# schema_current.net
KiCad netlist of a schematic drawn in EAGLE
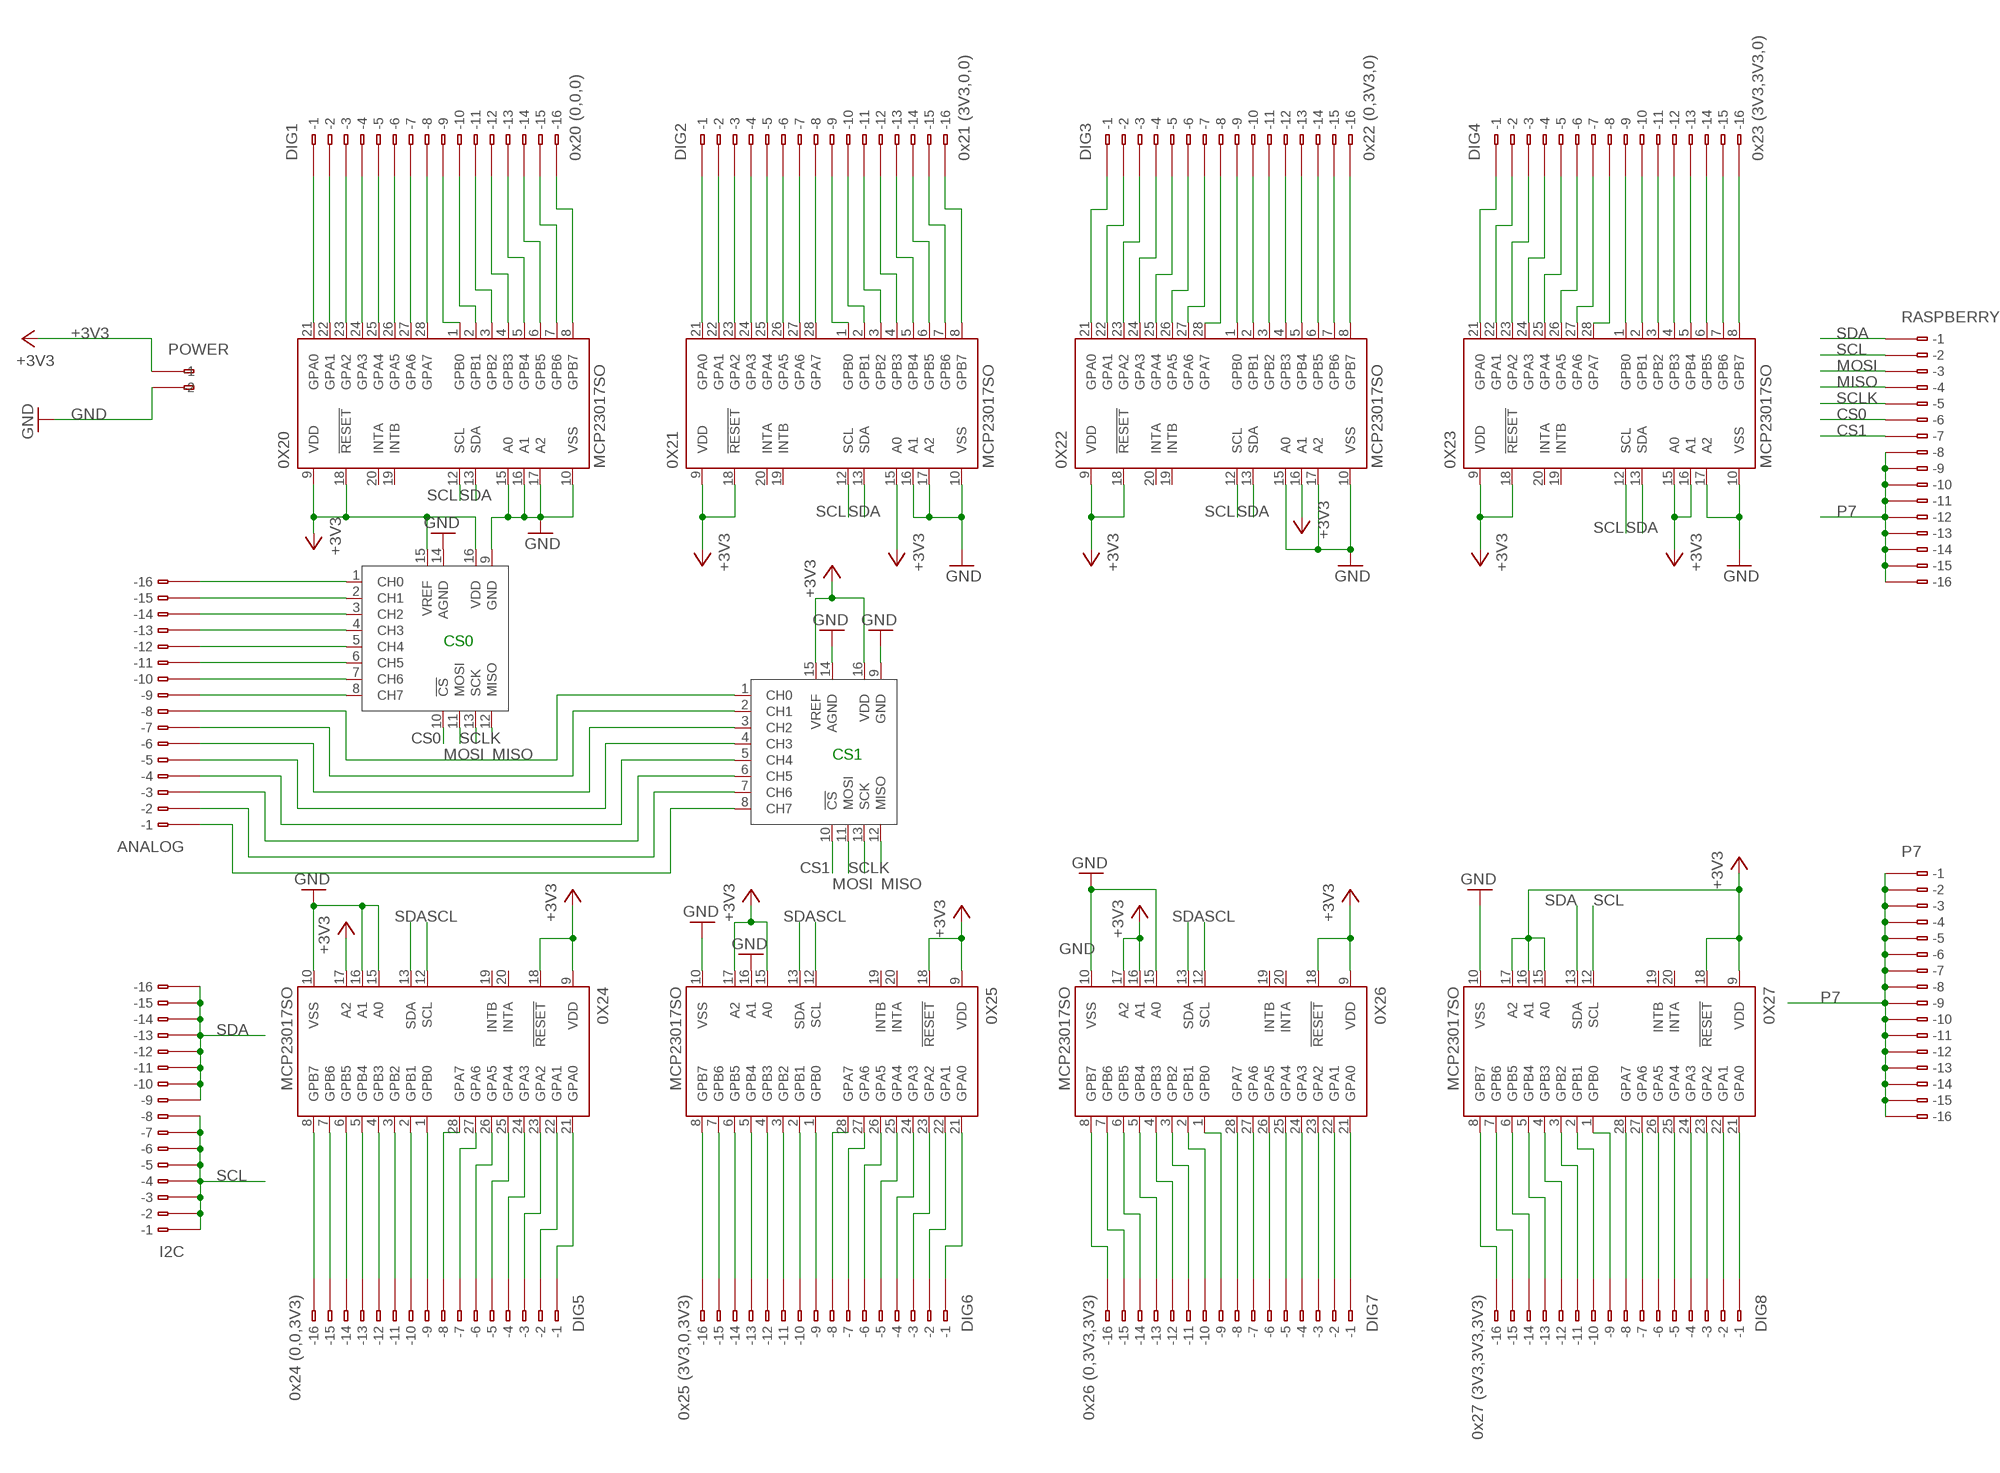
[diagram p0: schematic, sheet 1]

(export (version "E")
  (design (tool "Eeschema 10.0.6"))
  (components
    (comp (ref "0X20")
      (value "MCP23017SO")
      (footprint "eagle-import:SO28W")
      (fields (field (name "MF") "MICROCHIP") (field (name "MPN") "MCP23017-E/SO"))
      (libsource (lib "eagle-import") (part "MCP23017SO"))
    )
    (comp (ref "0X21")
      (value "MCP23017SO")
      (footprint "eagle-import:SO28W")
      (fields (field (name "MF") "MICROCHIP") (field (name "MPN") "MCP23017-E/SO"))
      (libsource (lib "eagle-import") (part "MCP23017SO"))
    )
    (comp (ref "0X22")
      (value "MCP23017SO")
      (footprint "eagle-import:SO28W")
      (fields (field (name "MF") "MICROCHIP") (field (name "MPN") "MCP23017-E/SO"))
      (libsource (lib "eagle-import") (part "MCP23017SO"))
    )
    (comp (ref "0X23")
      (value "MCP23017SO")
      (footprint "eagle-import:SO28W")
      (fields (field (name "MF") "MICROCHIP") (field (name "MPN") "MCP23017-E/SO"))
      (libsource (lib "eagle-import") (part "MCP23017SO"))
    )
    (comp (ref "0X24")
      (value "MCP23017SO")
      (footprint "eagle-import:SO28W")
      (fields (field (name "MF") "MICROCHIP") (field (name "MPN") "MCP23017-E/SO"))
      (libsource (lib "eagle-import") (part "MCP23017SO"))
    )
    (comp (ref "0X25")
      (value "MCP23017SO")
      (footprint "eagle-import:SO28W")
      (fields (field (name "MF") "MICROCHIP") (field (name "MPN") "MCP23017-E/SO"))
      (libsource (lib "eagle-import") (part "MCP23017SO"))
    )
    (comp (ref "0X26")
      (value "MCP23017SO")
      (footprint "eagle-import:SO28W")
      (fields (field (name "MF") "MICROCHIP") (field (name "MPN") "MCP23017-E/SO"))
      (libsource (lib "eagle-import") (part "MCP23017SO"))
    )
    (comp (ref "0X27")
      (value "MCP23017SO")
      (footprint "eagle-import:SO28W")
      (fields (field (name "MF") "MICROCHIP") (field (name "MPN") "MCP23017-E/SO"))
      (libsource (lib "eagle-import") (part "MCP23017SO"))
    )
    (comp (ref "ANALOG")
      (value "233-116")
      (footprint "eagle-import:233-116")
      (libsource (lib "eagle-import") (part "233-116"))
    )
    (comp (ref "DIG1")
      (value "0x20 (0,0,0)")
      (footprint "eagle-import:233-116")
      (fields (field (name "MPN") "233-116"))
      (libsource (lib "eagle-import") (part "233-116"))
    )
    (comp (ref "DIG2")
      (value "0x21 (3V3,0,0)")
      (footprint "eagle-import:233-116")
      (fields (field (name "MPN") "233-116"))
      (libsource (lib "eagle-import") (part "233-116"))
    )
    (comp (ref "DIG3")
      (value "0x22 (0,3V3,0)")
      (footprint "eagle-import:233-116")
      (fields (field (name "MPN") "233-116"))
      (libsource (lib "eagle-import") (part "233-116"))
    )
    (comp (ref "DIG4")
      (value "0x23 (3V3,3V3,0)")
      (footprint "eagle-import:233-116")
      (fields (field (name "MPN") "233-116"))
      (libsource (lib "eagle-import") (part "233-116"))
    )
    (comp (ref "DIG5")
      (value "0x24 (0,0,3V3)")
      (footprint "eagle-import:233-116")
      (fields (field (name "MPN") "233-116"))
      (libsource (lib "eagle-import") (part "233-116"))
    )
    (comp (ref "DIG6")
      (value "0x25 (3V3,0,3V3)")
      (footprint "eagle-import:233-116")
      (fields (field (name "MPN") "233-116"))
      (libsource (lib "eagle-import") (part "233-116"))
    )
    (comp (ref "DIG7")
      (value "0x26 (0,3V3,3V3)")
      (footprint "eagle-import:233-116")
      (fields (field (name "MPN") "233-116"))
      (libsource (lib "eagle-import") (part "233-116"))
    )
    (comp (ref "DIG8")
      (value "0x27 (3V3,3V3,3V3)")
      (footprint "eagle-import:233-116")
      (fields (field (name "MPN") "233-116"))
      (libsource (lib "eagle-import") (part "233-116"))
    )
    (comp (ref "I2C")
      (value "233-116")
      (footprint "eagle-import:233-116")
      (libsource (lib "eagle-import") (part "233-116"))
    )
    (comp (ref "MCP3008-CS0")
      (value "CS1")
      (footprint "eagle-import:DIL16")
      (libsource (lib "eagle-import") (part "MCP3008P"))
    )
    (comp (ref "MCP3008-CS1")
      (value "CS0")
      (footprint "eagle-import:DIL16")
      (libsource (lib "eagle-import") (part "MCP3008P"))
    )
    (comp (ref "P7")
      (value "233-116")
      (footprint "eagle-import:233-116")
      (libsource (lib "eagle-import") (part "233-116"))
    )
    (comp (ref "POWER")
      (value "233-102")
      (footprint "eagle-import:233-102")
      (libsource (lib "eagle-import") (part "233-102"))
    )
    (comp (ref "RASPBERRY")
      (value "233-116")
      (footprint "eagle-import:233-116")
      (libsource (lib "eagle-import") (part "233-116"))
    )
  )
  (nets
    (net (code "1") (name "+3V3") (class "Default")
      (node (ref "0X20") (pin "18") (pinfunction "~{RESET}_18") (pintype "input"))
      (node (ref "0X20") (pin "9") (pinfunction "VDD_9") (pintype "power_in"))
      (node (ref "0X21") (pin "15") (pinfunction "A0_15") (pintype "input"))
      (node (ref "0X21") (pin "18") (pinfunction "~{RESET}_18") (pintype "input"))
      (node (ref "0X21") (pin "9") (pinfunction "VDD_9") (pintype "power_in"))
      (node (ref "0X22") (pin "16") (pinfunction "A1_16") (pintype "input"))
      (node (ref "0X22") (pin "18") (pinfunction "~{RESET}_18") (pintype "input"))
      (node (ref "0X22") (pin "9") (pinfunction "VDD_9") (pintype "power_in"))
      (node (ref "0X23") (pin "15") (pinfunction "A0_15") (pintype "input"))
      (node (ref "0X23") (pin "16") (pinfunction "A1_16") (pintype "input"))
      (node (ref "0X23") (pin "18") (pinfunction "~{RESET}_18") (pintype "input"))
      (node (ref "0X23") (pin "9") (pinfunction "VDD_9") (pintype "power_in"))
      (node (ref "0X24") (pin "17") (pinfunction "A2_17") (pintype "input"))
      (node (ref "0X24") (pin "18") (pinfunction "~{RESET}_18") (pintype "input"))
      (node (ref "0X24") (pin "9") (pinfunction "VDD_9") (pintype "power_in"))
      (node (ref "0X25") (pin "15") (pinfunction "A0_15") (pintype "input"))
      (node (ref "0X25") (pin "17") (pinfunction "A2_17") (pintype "input"))
      (node (ref "0X25") (pin "18") (pinfunction "~{RESET}_18") (pintype "input"))
      (node (ref "0X25") (pin "9") (pinfunction "VDD_9") (pintype "power_in"))
      (node (ref "0X26") (pin "16") (pinfunction "A1_16") (pintype "input"))
      (node (ref "0X26") (pin "17") (pinfunction "A2_17") (pintype "input"))
      (node (ref "0X26") (pin "18") (pinfunction "~{RESET}_18") (pintype "input"))
      (node (ref "0X26") (pin "9") (pinfunction "VDD_9") (pintype "power_in"))
      (node (ref "0X27") (pin "15") (pinfunction "A0_15") (pintype "input"))
      (node (ref "0X27") (pin "16") (pinfunction "A1_16") (pintype "input"))
      (node (ref "0X27") (pin "17") (pinfunction "A2_17") (pintype "input"))
      (node (ref "0X27") (pin "18") (pinfunction "~{RESET}_18") (pintype "input"))
      (node (ref "0X27") (pin "9") (pinfunction "VDD_9") (pintype "power_in"))
      (node (ref "MCP3008-CS0") (pin "15") (pinfunction "VREF_15") (pintype "power_in"))
      (node (ref "MCP3008-CS0") (pin "16") (pinfunction "VDD_16") (pintype "power_in"))
      (node (ref "MCP3008-CS1") (pin "15") (pinfunction "VREF_15") (pintype "power_in"))
      (node (ref "MCP3008-CS1") (pin "16") (pinfunction "VDD_16") (pintype "power_in"))
      (node (ref "POWER") (pin "A1") (pinfunction "-1_A1") (pintype "passive"))
    )
    (net (code "2") (name "/CS0") (class "Default")
      (node (ref "MCP3008-CS0") (pin "10") (pinfunction "~{CS}_10") (pintype "input"))
      (node (ref "RASPBERRY") (pin "B6") (pinfunction "B-6_B6") (pintype "passive"))
    )
    (net (code "3") (name "/CS1") (class "Default")
      (node (ref "MCP3008-CS1") (pin "10") (pinfunction "~{CS}_10") (pintype "input"))
      (node (ref "RASPBERRY") (pin "B7") (pinfunction "B-7_B7") (pintype "passive"))
    )
    (net (code "4") (name "/MISO") (class "Default")
      (node (ref "MCP3008-CS0") (pin "12") (pinfunction "MISO_12") (pintype "output"))
      (node (ref "MCP3008-CS1") (pin "12") (pinfunction "MISO_12") (pintype "output"))
      (node (ref "RASPBERRY") (pin "B4") (pinfunction "B-4_B4") (pintype "passive"))
    )
    (net (code "5") (name "/MOSI") (class "Default")
      (node (ref "MCP3008-CS0") (pin "11") (pinfunction "MOSI_11") (pintype "input"))
      (node (ref "MCP3008-CS1") (pin "11") (pinfunction "MOSI_11") (pintype "input"))
      (node (ref "RASPBERRY") (pin "B3") (pinfunction "B-3_B3") (pintype "passive"))
    )
    (net (code "6") (name "/P7") (class "Default")
      (node (ref "P7") (pin "B1") (pinfunction "B-1_B1") (pintype "passive"))
      (node (ref "P7") (pin "B10") (pinfunction "B-10_B10") (pintype "passive"))
      (node (ref "P7") (pin "B11") (pinfunction "B-11_B11") (pintype "passive"))
      (node (ref "P7") (pin "B12") (pinfunction "B-12_B12") (pintype "passive"))
      (node (ref "P7") (pin "B13") (pinfunction "B-13_B13") (pintype "passive"))
      (node (ref "P7") (pin "B14") (pinfunction "B-14_B14") (pintype "passive"))
      (node (ref "P7") (pin "B15") (pinfunction "B-15_B15") (pintype "passive"))
      (node (ref "P7") (pin "B16") (pinfunction "B-16_B16") (pintype "passive"))
      (node (ref "P7") (pin "B2") (pinfunction "B-2_B2") (pintype "passive"))
      (node (ref "P7") (pin "B3") (pinfunction "B-3_B3") (pintype "passive"))
      (node (ref "P7") (pin "B4") (pinfunction "B-4_B4") (pintype "passive"))
      (node (ref "P7") (pin "B5") (pinfunction "B-5_B5") (pintype "passive"))
      (node (ref "P7") (pin "B6") (pinfunction "B-6_B6") (pintype "passive"))
      (node (ref "P7") (pin "B7") (pinfunction "B-7_B7") (pintype "passive"))
      (node (ref "P7") (pin "B8") (pinfunction "B-8_B8") (pintype "passive"))
      (node (ref "P7") (pin "B9") (pinfunction "B-9_B9") (pintype "passive"))
      (node (ref "RASPBERRY") (pin "B10") (pinfunction "B-10_B10") (pintype "passive"))
      (node (ref "RASPBERRY") (pin "B11") (pinfunction "B-11_B11") (pintype "passive"))
      (node (ref "RASPBERRY") (pin "B12") (pinfunction "B-12_B12") (pintype "passive"))
      (node (ref "RASPBERRY") (pin "B13") (pinfunction "B-13_B13") (pintype "passive"))
      (node (ref "RASPBERRY") (pin "B14") (pinfunction "B-14_B14") (pintype "passive"))
      (node (ref "RASPBERRY") (pin "B15") (pinfunction "B-15_B15") (pintype "passive"))
      (node (ref "RASPBERRY") (pin "B16") (pinfunction "B-16_B16") (pintype "passive"))
      (node (ref "RASPBERRY") (pin "B8") (pinfunction "B-8_B8") (pintype "passive"))
      (node (ref "RASPBERRY") (pin "B9") (pinfunction "B-9_B9") (pintype "passive"))
    )
    (net (code "7") (name "/SCL") (class "Default")
      (node (ref "0X20") (pin "12") (pinfunction "SCL_12") (pintype "input"))
      (node (ref "0X21") (pin "12") (pinfunction "SCL_12") (pintype "input"))
      (node (ref "0X22") (pin "12") (pinfunction "SCL_12") (pintype "input"))
      (node (ref "0X23") (pin "12") (pinfunction "SCL_12") (pintype "input"))
      (node (ref "0X24") (pin "12") (pinfunction "SCL_12") (pintype "input"))
      (node (ref "0X25") (pin "12") (pinfunction "SCL_12") (pintype "input"))
      (node (ref "0X26") (pin "12") (pinfunction "SCL_12") (pintype "input"))
      (node (ref "0X27") (pin "12") (pinfunction "SCL_12") (pintype "input"))
      (node (ref "I2C") (pin "B1") (pinfunction "B-1_B1") (pintype "passive"))
      (node (ref "I2C") (pin "B2") (pinfunction "B-2_B2") (pintype "passive"))
      (node (ref "I2C") (pin "B3") (pinfunction "B-3_B3") (pintype "passive"))
      (node (ref "I2C") (pin "B4") (pinfunction "B-4_B4") (pintype "passive"))
      (node (ref "I2C") (pin "B5") (pinfunction "B-5_B5") (pintype "passive"))
      (node (ref "I2C") (pin "B6") (pinfunction "B-6_B6") (pintype "passive"))
      (node (ref "I2C") (pin "B7") (pinfunction "B-7_B7") (pintype "passive"))
      (node (ref "I2C") (pin "B8") (pinfunction "B-8_B8") (pintype "passive"))
      (node (ref "RASPBERRY") (pin "B2") (pinfunction "B-2_B2") (pintype "passive"))
    )
    (net (code "8") (name "/SCLK") (class "Default")
      (node (ref "MCP3008-CS0") (pin "13") (pinfunction "SCK_13") (pintype "input"))
      (node (ref "MCP3008-CS1") (pin "13") (pinfunction "SCK_13") (pintype "input"))
      (node (ref "RASPBERRY") (pin "B5") (pinfunction "B-5_B5") (pintype "passive"))
    )
    (net (code "9") (name "/SDA") (class "Default")
      (node (ref "0X20") (pin "13") (pinfunction "SDA_13") (pintype "bidirectional"))
      (node (ref "0X21") (pin "13") (pinfunction "SDA_13") (pintype "bidirectional"))
      (node (ref "0X22") (pin "13") (pinfunction "SDA_13") (pintype "bidirectional"))
      (node (ref "0X23") (pin "13") (pinfunction "SDA_13") (pintype "bidirectional"))
      (node (ref "0X24") (pin "13") (pinfunction "SDA_13") (pintype "bidirectional"))
      (node (ref "0X25") (pin "13") (pinfunction "SDA_13") (pintype "bidirectional"))
      (node (ref "0X26") (pin "13") (pinfunction "SDA_13") (pintype "bidirectional"))
      (node (ref "0X27") (pin "13") (pinfunction "SDA_13") (pintype "bidirectional"))
      (node (ref "I2C") (pin "B10") (pinfunction "B-10_B10") (pintype "passive"))
      (node (ref "I2C") (pin "B11") (pinfunction "B-11_B11") (pintype "passive"))
      (node (ref "I2C") (pin "B12") (pinfunction "B-12_B12") (pintype "passive"))
      (node (ref "I2C") (pin "B13") (pinfunction "B-13_B13") (pintype "passive"))
      (node (ref "I2C") (pin "B14") (pinfunction "B-14_B14") (pintype "passive"))
      (node (ref "I2C") (pin "B15") (pinfunction "B-15_B15") (pintype "passive"))
      (node (ref "I2C") (pin "B16") (pinfunction "B-16_B16") (pintype "passive"))
      (node (ref "I2C") (pin "B9") (pinfunction "B-9_B9") (pintype "passive"))
      (node (ref "RASPBERRY") (pin "B1") (pinfunction "B-1_B1") (pintype "passive"))
    )
    (net (code "10") (name "GND") (class "Default")
      (node (ref "0X20") (pin "10") (pinfunction "VSS_10") (pintype "power_in"))
      (node (ref "0X20") (pin "15") (pinfunction "A0_15") (pintype "input"))
      (node (ref "0X20") (pin "16") (pinfunction "A1_16") (pintype "input"))
      (node (ref "0X20") (pin "17") (pinfunction "A2_17") (pintype "input"))
      (node (ref "0X21") (pin "10") (pinfunction "VSS_10") (pintype "power_in"))
      (node (ref "0X21") (pin "16") (pinfunction "A1_16") (pintype "input"))
      (node (ref "0X21") (pin "17") (pinfunction "A2_17") (pintype "input"))
      (node (ref "0X22") (pin "10") (pinfunction "VSS_10") (pintype "power_in"))
      (node (ref "0X22") (pin "15") (pinfunction "A0_15") (pintype "input"))
      (node (ref "0X22") (pin "17") (pinfunction "A2_17") (pintype "input"))
      (node (ref "0X23") (pin "10") (pinfunction "VSS_10") (pintype "power_in"))
      (node (ref "0X23") (pin "17") (pinfunction "A2_17") (pintype "input"))
      (node (ref "0X24") (pin "10") (pinfunction "VSS_10") (pintype "power_in"))
      (node (ref "0X24") (pin "15") (pinfunction "A0_15") (pintype "input"))
      (node (ref "0X24") (pin "16") (pinfunction "A1_16") (pintype "input"))
      (node (ref "0X25") (pin "10") (pinfunction "VSS_10") (pintype "power_in"))
      (node (ref "0X25") (pin "16") (pinfunction "A1_16") (pintype "input"))
      (node (ref "0X26") (pin "10") (pinfunction "VSS_10") (pintype "power_in"))
      (node (ref "0X26") (pin "15") (pinfunction "A0_15") (pintype "input"))
      (node (ref "0X27") (pin "10") (pinfunction "VSS_10") (pintype "power_in"))
      (node (ref "MCP3008-CS0") (pin "14") (pinfunction "AGND_14") (pintype "power_in"))
      (node (ref "MCP3008-CS0") (pin "9") (pinfunction "GND_9") (pintype "power_in"))
      (node (ref "MCP3008-CS1") (pin "14") (pinfunction "AGND_14") (pintype "power_in"))
      (node (ref "MCP3008-CS1") (pin "9") (pinfunction "GND_9") (pintype "power_in"))
      (node (ref "POWER") (pin "A2") (pinfunction "-2_A2") (pintype "passive"))
    )
    (net (code "11") (name "Net-(0X20-GPA0)") (class "Default")
      (node (ref "0X20") (pin "21") (pinfunction "GPA0_21") (pintype "bidirectional"))
      (node (ref "DIG1") (pin "B1") (pinfunction "B-1_B1") (pintype "passive"))
    )
    (net (code "12") (name "Net-(0X20-GPA1)") (class "Default")
      (node (ref "0X20") (pin "22") (pinfunction "GPA1_22") (pintype "bidirectional"))
      (node (ref "DIG1") (pin "B2") (pinfunction "B-2_B2") (pintype "passive"))
    )
    (net (code "13") (name "Net-(0X20-GPA2)") (class "Default")
      (node (ref "0X20") (pin "23") (pinfunction "GPA2_23") (pintype "bidirectional"))
      (node (ref "DIG1") (pin "B3") (pinfunction "B-3_B3") (pintype "passive"))
    )
    (net (code "14") (name "Net-(0X20-GPA3)") (class "Default")
      (node (ref "0X20") (pin "24") (pinfunction "GPA3_24") (pintype "bidirectional"))
      (node (ref "DIG1") (pin "B4") (pinfunction "B-4_B4") (pintype "passive"))
    )
    (net (code "15") (name "Net-(0X20-GPA4)") (class "Default")
      (node (ref "0X20") (pin "25") (pinfunction "GPA4_25") (pintype "bidirectional"))
      (node (ref "DIG1") (pin "B5") (pinfunction "B-5_B5") (pintype "passive"))
    )
    (net (code "16") (name "Net-(0X20-GPA5)") (class "Default")
      (node (ref "0X20") (pin "26") (pinfunction "GPA5_26") (pintype "bidirectional"))
      (node (ref "DIG1") (pin "B6") (pinfunction "B-6_B6") (pintype "passive"))
    )
    (net (code "17") (name "Net-(0X20-GPA6)") (class "Default")
      (node (ref "0X20") (pin "27") (pinfunction "GPA6_27") (pintype "bidirectional"))
      (node (ref "DIG1") (pin "B7") (pinfunction "B-7_B7") (pintype "passive"))
    )
    (net (code "18") (name "Net-(0X20-GPA7)") (class "Default")
      (node (ref "0X20") (pin "28") (pinfunction "GPA7_28") (pintype "bidirectional"))
      (node (ref "DIG1") (pin "B8") (pinfunction "B-8_B8") (pintype "passive"))
    )
    (net (code "19") (name "Net-(0X20-GPB0)") (class "Default")
      (node (ref "0X20") (pin "1") (pinfunction "GPB0_1") (pintype "bidirectional"))
      (node (ref "DIG1") (pin "B9") (pinfunction "B-9_B9") (pintype "passive"))
    )
    (net (code "20") (name "Net-(0X20-GPB1)") (class "Default")
      (node (ref "0X20") (pin "2") (pinfunction "GPB1_2") (pintype "bidirectional"))
      (node (ref "DIG1") (pin "B10") (pinfunction "B-10_B10") (pintype "passive"))
    )
    (net (code "21") (name "Net-(0X20-GPB2)") (class "Default")
      (node (ref "0X20") (pin "3") (pinfunction "GPB2_3") (pintype "bidirectional"))
      (node (ref "DIG1") (pin "B11") (pinfunction "B-11_B11") (pintype "passive"))
    )
    (net (code "22") (name "Net-(0X20-GPB3)") (class "Default")
      (node (ref "0X20") (pin "4") (pinfunction "GPB3_4") (pintype "bidirectional"))
      (node (ref "DIG1") (pin "B12") (pinfunction "B-12_B12") (pintype "passive"))
    )
    (net (code "23") (name "Net-(0X20-GPB4)") (class "Default")
      (node (ref "0X20") (pin "5") (pinfunction "GPB4_5") (pintype "bidirectional"))
      (node (ref "DIG1") (pin "B13") (pinfunction "B-13_B13") (pintype "passive"))
    )
    (net (code "24") (name "Net-(0X20-GPB5)") (class "Default")
      (node (ref "0X20") (pin "6") (pinfunction "GPB5_6") (pintype "bidirectional"))
      (node (ref "DIG1") (pin "B14") (pinfunction "B-14_B14") (pintype "passive"))
    )
    (net (code "25") (name "Net-(0X20-GPB6)") (class "Default")
      (node (ref "0X20") (pin "7") (pinfunction "GPB6_7") (pintype "bidirectional"))
      (node (ref "DIG1") (pin "B15") (pinfunction "B-15_B15") (pintype "passive"))
    )
    (net (code "26") (name "Net-(0X20-GPB7)") (class "Default")
      (node (ref "0X20") (pin "8") (pinfunction "GPB7_8") (pintype "bidirectional"))
      (node (ref "DIG1") (pin "B16") (pinfunction "B-16_B16") (pintype "passive"))
    )
    (net (code "27") (name "Net-(0X21-GPA0)") (class "Default")
      (node (ref "0X21") (pin "21") (pinfunction "GPA0_21") (pintype "bidirectional"))
      (node (ref "DIG2") (pin "B1") (pinfunction "B-1_B1") (pintype "passive"))
    )
    (net (code "28") (name "Net-(0X21-GPA1)") (class "Default")
      (node (ref "0X21") (pin "22") (pinfunction "GPA1_22") (pintype "bidirectional"))
      (node (ref "DIG2") (pin "B2") (pinfunction "B-2_B2") (pintype "passive"))
    )
    (net (code "29") (name "Net-(0X21-GPA2)") (class "Default")
      (node (ref "0X21") (pin "23") (pinfunction "GPA2_23") (pintype "bidirectional"))
      (node (ref "DIG2") (pin "B3") (pinfunction "B-3_B3") (pintype "passive"))
    )
    (net (code "30") (name "Net-(0X21-GPA3)") (class "Default")
      (node (ref "0X21") (pin "24") (pinfunction "GPA3_24") (pintype "bidirectional"))
      (node (ref "DIG2") (pin "B4") (pinfunction "B-4_B4") (pintype "passive"))
    )
    (net (code "31") (name "Net-(0X21-GPA4)") (class "Default")
      (node (ref "0X21") (pin "25") (pinfunction "GPA4_25") (pintype "bidirectional"))
      (node (ref "DIG2") (pin "B5") (pinfunction "B-5_B5") (pintype "passive"))
    )
    (net (code "32") (name "Net-(0X21-GPA5)") (class "Default")
      (node (ref "0X21") (pin "26") (pinfunction "GPA5_26") (pintype "bidirectional"))
      (node (ref "DIG2") (pin "B6") (pinfunction "B-6_B6") (pintype "passive"))
    )
    (net (code "33") (name "Net-(0X21-GPA6)") (class "Default")
      (node (ref "0X21") (pin "27") (pinfunction "GPA6_27") (pintype "bidirectional"))
      (node (ref "DIG2") (pin "B7") (pinfunction "B-7_B7") (pintype "passive"))
    )
    (net (code "34") (name "Net-(0X21-GPA7)") (class "Default")
      (node (ref "0X21") (pin "28") (pinfunction "GPA7_28") (pintype "bidirectional"))
      (node (ref "DIG2") (pin "B8") (pinfunction "B-8_B8") (pintype "passive"))
    )
    (net (code "35") (name "Net-(0X21-GPB0)") (class "Default")
      (node (ref "0X21") (pin "1") (pinfunction "GPB0_1") (pintype "bidirectional"))
      (node (ref "DIG2") (pin "B9") (pinfunction "B-9_B9") (pintype "passive"))
    )
    (net (code "36") (name "Net-(0X21-GPB1)") (class "Default")
      (node (ref "0X21") (pin "2") (pinfunction "GPB1_2") (pintype "bidirectional"))
      (node (ref "DIG2") (pin "B10") (pinfunction "B-10_B10") (pintype "passive"))
    )
    (net (code "37") (name "Net-(0X21-GPB2)") (class "Default")
      (node (ref "0X21") (pin "3") (pinfunction "GPB2_3") (pintype "bidirectional"))
      (node (ref "DIG2") (pin "B11") (pinfunction "B-11_B11") (pintype "passive"))
    )
    (net (code "38") (name "Net-(0X21-GPB3)") (class "Default")
      (node (ref "0X21") (pin "4") (pinfunction "GPB3_4") (pintype "bidirectional"))
      (node (ref "DIG2") (pin "B12") (pinfunction "B-12_B12") (pintype "passive"))
    )
    (net (code "39") (name "Net-(0X21-GPB4)") (class "Default")
      (node (ref "0X21") (pin "5") (pinfunction "GPB4_5") (pintype "bidirectional"))
      (node (ref "DIG2") (pin "B13") (pinfunction "B-13_B13") (pintype "passive"))
    )
    (net (code "40") (name "Net-(0X21-GPB5)") (class "Default")
      (node (ref "0X21") (pin "6") (pinfunction "GPB5_6") (pintype "bidirectional"))
      (node (ref "DIG2") (pin "B14") (pinfunction "B-14_B14") (pintype "passive"))
    )
    (net (code "41") (name "Net-(0X21-GPB6)") (class "Default")
      (node (ref "0X21") (pin "7") (pinfunction "GPB6_7") (pintype "bidirectional"))
      (node (ref "DIG2") (pin "B15") (pinfunction "B-15_B15") (pintype "passive"))
    )
    (net (code "42") (name "Net-(0X21-GPB7)") (class "Default")
      (node (ref "0X21") (pin "8") (pinfunction "GPB7_8") (pintype "bidirectional"))
      (node (ref "DIG2") (pin "B16") (pinfunction "B-16_B16") (pintype "passive"))
    )
    (net (code "43") (name "Net-(0X22-GPA0)") (class "Default")
      (node (ref "0X22") (pin "21") (pinfunction "GPA0_21") (pintype "bidirectional"))
      (node (ref "DIG3") (pin "B1") (pinfunction "B-1_B1") (pintype "passive"))
    )
    (net (code "44") (name "Net-(0X22-GPA1)") (class "Default")
      (node (ref "0X22") (pin "22") (pinfunction "GPA1_22") (pintype "bidirectional"))
      (node (ref "DIG3") (pin "B2") (pinfunction "B-2_B2") (pintype "passive"))
    )
    (net (code "45") (name "Net-(0X22-GPA2)") (class "Default")
      (node (ref "0X22") (pin "23") (pinfunction "GPA2_23") (pintype "bidirectional"))
      (node (ref "DIG3") (pin "B3") (pinfunction "B-3_B3") (pintype "passive"))
    )
    (net (code "46") (name "Net-(0X22-GPA3)") (class "Default")
      (node (ref "0X22") (pin "24") (pinfunction "GPA3_24") (pintype "bidirectional"))
      (node (ref "DIG3") (pin "B4") (pinfunction "B-4_B4") (pintype "passive"))
    )
    (net (code "47") (name "Net-(0X22-GPA4)") (class "Default")
      (node (ref "0X22") (pin "25") (pinfunction "GPA4_25") (pintype "bidirectional"))
      (node (ref "DIG3") (pin "B5") (pinfunction "B-5_B5") (pintype "passive"))
    )
    (net (code "48") (name "Net-(0X22-GPA5)") (class "Default")
      (node (ref "0X22") (pin "26") (pinfunction "GPA5_26") (pintype "bidirectional"))
      (node (ref "DIG3") (pin "B6") (pinfunction "B-6_B6") (pintype "passive"))
    )
    (net (code "49") (name "Net-(0X22-GPA6)") (class "Default")
      (node (ref "0X22") (pin "27") (pinfunction "GPA6_27") (pintype "bidirectional"))
      (node (ref "DIG3") (pin "B7") (pinfunction "B-7_B7") (pintype "passive"))
    )
    (net (code "50") (name "Net-(0X22-GPA7)") (class "Default")
      (node (ref "0X22") (pin "28") (pinfunction "GPA7_28") (pintype "bidirectional"))
      (node (ref "DIG3") (pin "B8") (pinfunction "B-8_B8") (pintype "passive"))
    )
    (net (code "51") (name "Net-(0X22-GPB0)") (class "Default")
      (node (ref "0X22") (pin "1") (pinfunction "GPB0_1") (pintype "bidirectional"))
      (node (ref "DIG3") (pin "B9") (pinfunction "B-9_B9") (pintype "passive"))
    )
    (net (code "52") (name "Net-(0X22-GPB1)") (class "Default")
      (node (ref "0X22") (pin "2") (pinfunction "GPB1_2") (pintype "bidirectional"))
      (node (ref "DIG3") (pin "B10") (pinfunction "B-10_B10") (pintype "passive"))
    )
    (net (code "53") (name "Net-(0X22-GPB2)") (class "Default")
      (node (ref "0X22") (pin "3") (pinfunction "GPB2_3") (pintype "bidirectional"))
      (node (ref "DIG3") (pin "B11") (pinfunction "B-11_B11") (pintype "passive"))
    )
    (net (code "54") (name "Net-(0X22-GPB3)") (class "Default")
      (node (ref "0X22") (pin "4") (pinfunction "GPB3_4") (pintype "bidirectional"))
      (node (ref "DIG3") (pin "B12") (pinfunction "B-12_B12") (pintype "passive"))
    )
    (net (code "55") (name "Net-(0X22-GPB4)") (class "Default")
      (node (ref "0X22") (pin "5") (pinfunction "GPB4_5") (pintype "bidirectional"))
      (node (ref "DIG3") (pin "B13") (pinfunction "B-13_B13") (pintype "passive"))
    )
    (net (code "56") (name "Net-(0X22-GPB5)") (class "Default")
      (node (ref "0X22") (pin "6") (pinfunction "GPB5_6") (pintype "bidirectional"))
      (node (ref "DIG3") (pin "B14") (pinfunction "B-14_B14") (pintype "passive"))
    )
    (net (code "57") (name "Net-(0X22-GPB6)") (class "Default")
      (node (ref "0X22") (pin "7") (pinfunction "GPB6_7") (pintype "bidirectional"))
      (node (ref "DIG3") (pin "B15") (pinfunction "B-15_B15") (pintype "passive"))
    )
    (net (code "58") (name "Net-(0X22-GPB7)") (class "Default")
      (node (ref "0X22") (pin "8") (pinfunction "GPB7_8") (pintype "bidirectional"))
      (node (ref "DIG3") (pin "B16") (pinfunction "B-16_B16") (pintype "passive"))
    )
    (net (code "59") (name "Net-(0X23-GPA0)") (class "Default")
      (node (ref "0X23") (pin "21") (pinfunction "GPA0_21") (pintype "bidirectional"))
      (node (ref "DIG4") (pin "B1") (pinfunction "B-1_B1") (pintype "passive"))
    )
    (net (code "60") (name "Net-(0X23-GPA1)") (class "Default")
      (node (ref "0X23") (pin "22") (pinfunction "GPA1_22") (pintype "bidirectional"))
      (node (ref "DIG4") (pin "B2") (pinfunction "B-2_B2") (pintype "passive"))
    )
    (net (code "61") (name "Net-(0X23-GPA2)") (class "Default")
      (node (ref "0X23") (pin "23") (pinfunction "GPA2_23") (pintype "bidirectional"))
      (node (ref "DIG4") (pin "B3") (pinfunction "B-3_B3") (pintype "passive"))
    )
    (net (code "62") (name "Net-(0X23-GPA3)") (class "Default")
      (node (ref "0X23") (pin "24") (pinfunction "GPA3_24") (pintype "bidirectional"))
      (node (ref "DIG4") (pin "B4") (pinfunction "B-4_B4") (pintype "passive"))
    )
    (net (code "63") (name "Net-(0X23-GPA4)") (class "Default")
      (node (ref "0X23") (pin "25") (pinfunction "GPA4_25") (pintype "bidirectional"))
      (node (ref "DIG4") (pin "B5") (pinfunction "B-5_B5") (pintype "passive"))
    )
    (net (code "64") (name "Net-(0X23-GPA5)") (class "Default")
      (node (ref "0X23") (pin "26") (pinfunction "GPA5_26") (pintype "bidirectional"))
      (node (ref "DIG4") (pin "B6") (pinfunction "B-6_B6") (pintype "passive"))
    )
    (net (code "65") (name "Net-(0X23-GPA6)") (class "Default")
      (node (ref "0X23") (pin "27") (pinfunction "GPA6_27") (pintype "bidirectional"))
      (node (ref "DIG4") (pin "B7") (pinfunction "B-7_B7") (pintype "passive"))
    )
    (net (code "66") (name "Net-(0X23-GPA7)") (class "Default")
      (node (ref "0X23") (pin "28") (pinfunction "GPA7_28") (pintype "bidirectional"))
      (node (ref "DIG4") (pin "B8") (pinfunction "B-8_B8") (pintype "passive"))
    )
    (net (code "67") (name "Net-(0X23-GPB0)") (class "Default")
      (node (ref "0X23") (pin "1") (pinfunction "GPB0_1") (pintype "bidirectional"))
      (node (ref "DIG4") (pin "B9") (pinfunction "B-9_B9") (pintype "passive"))
    )
    (net (code "68") (name "Net-(0X23-GPB1)") (class "Default")
      (node (ref "0X23") (pin "2") (pinfunction "GPB1_2") (pintype "bidirectional"))
      (node (ref "DIG4") (pin "B10") (pinfunction "B-10_B10") (pintype "passive"))
    )
    (net (code "69") (name "Net-(0X23-GPB2)") (class "Default")
      (node (ref "0X23") (pin "3") (pinfunction "GPB2_3") (pintype "bidirectional"))
      (node (ref "DIG4") (pin "B11") (pinfunction "B-11_B11") (pintype "passive"))
    )
    (net (code "70") (name "Net-(0X23-GPB3)") (class "Default")
      (node (ref "0X23") (pin "4") (pinfunction "GPB3_4") (pintype "bidirectional"))
      (node (ref "DIG4") (pin "B12") (pinfunction "B-12_B12") (pintype "passive"))
    )
    (net (code "71") (name "Net-(0X23-GPB4)") (class "Default")
      (node (ref "0X23") (pin "5") (pinfunction "GPB4_5") (pintype "bidirectional"))
      (node (ref "DIG4") (pin "B13") (pinfunction "B-13_B13") (pintype "passive"))
    )
    (net (code "72") (name "Net-(0X23-GPB5)") (class "Default")
      (node (ref "0X23") (pin "6") (pinfunction "GPB5_6") (pintype "bidirectional"))
      (node (ref "DIG4") (pin "B14") (pinfunction "B-14_B14") (pintype "passive"))
    )
    (net (code "73") (name "Net-(0X23-GPB6)") (class "Default")
      (node (ref "0X23") (pin "7") (pinfunction "GPB6_7") (pintype "bidirectional"))
      (node (ref "DIG4") (pin "B15") (pinfunction "B-15_B15") (pintype "passive"))
    )
    (net (code "74") (name "Net-(0X23-GPB7)") (class "Default")
      (node (ref "0X23") (pin "8") (pinfunction "GPB7_8") (pintype "bidirectional"))
      (node (ref "DIG4") (pin "B16") (pinfunction "B-16_B16") (pintype "passive"))
    )
    (net (code "75") (name "Net-(0X24-GPA0)") (class "Default")
      (node (ref "0X24") (pin "21") (pinfunction "GPA0_21") (pintype "bidirectional"))
      (node (ref "DIG5") (pin "B1") (pinfunction "B-1_B1") (pintype "passive"))
    )
    (net (code "76") (name "Net-(0X24-GPA1)") (class "Default")
      (node (ref "0X24") (pin "22") (pinfunction "GPA1_22") (pintype "bidirectional"))
      (node (ref "DIG5") (pin "B2") (pinfunction "B-2_B2") (pintype "passive"))
    )
    (net (code "77") (name "Net-(0X24-GPA2)") (class "Default")
      (node (ref "0X24") (pin "23") (pinfunction "GPA2_23") (pintype "bidirectional"))
      (node (ref "DIG5") (pin "B3") (pinfunction "B-3_B3") (pintype "passive"))
    )
    (net (code "78") (name "Net-(0X24-GPA3)") (class "Default")
      (node (ref "0X24") (pin "24") (pinfunction "GPA3_24") (pintype "bidirectional"))
      (node (ref "DIG5") (pin "B4") (pinfunction "B-4_B4") (pintype "passive"))
    )
    (net (code "79") (name "Net-(0X24-GPA4)") (class "Default")
      (node (ref "0X24") (pin "25") (pinfunction "GPA4_25") (pintype "bidirectional"))
      (node (ref "DIG5") (pin "B5") (pinfunction "B-5_B5") (pintype "passive"))
    )
    (net (code "80") (name "Net-(0X24-GPA5)") (class "Default")
      (node (ref "0X24") (pin "26") (pinfunction "GPA5_26") (pintype "bidirectional"))
      (node (ref "DIG5") (pin "B6") (pinfunction "B-6_B6") (pintype "passive"))
    )
    (net (code "81") (name "Net-(0X24-GPA6)") (class "Default")
      (node (ref "0X24") (pin "27") (pinfunction "GPA6_27") (pintype "bidirectional"))
      (node (ref "DIG5") (pin "B7") (pinfunction "B-7_B7") (pintype "passive"))
    )
    (net (code "82") (name "Net-(0X24-GPA7)") (class "Default")
      (node (ref "0X24") (pin "28") (pinfunction "GPA7_28") (pintype "bidirectional"))
      (node (ref "DIG5") (pin "B8") (pinfunction "B-8_B8") (pintype "passive"))
    )
    (net (code "83") (name "Net-(0X24-GPB0)") (class "Default")
      (node (ref "0X24") (pin "1") (pinfunction "GPB0_1") (pintype "bidirectional"))
      (node (ref "DIG5") (pin "B9") (pinfunction "B-9_B9") (pintype "passive"))
    )
    (net (code "84") (name "Net-(0X24-GPB1)") (class "Default")
      (node (ref "0X24") (pin "2") (pinfunction "GPB1_2") (pintype "bidirectional"))
      (node (ref "DIG5") (pin "B10") (pinfunction "B-10_B10") (pintype "passive"))
    )
    (net (code "85") (name "Net-(0X24-GPB2)") (class "Default")
      (node (ref "0X24") (pin "3") (pinfunction "GPB2_3") (pintype "bidirectional"))
      (node (ref "DIG5") (pin "B11") (pinfunction "B-11_B11") (pintype "passive"))
    )
    (net (code "86") (name "Net-(0X24-GPB3)") (class "Default")
      (node (ref "0X24") (pin "4") (pinfunction "GPB3_4") (pintype "bidirectional"))
      (node (ref "DIG5") (pin "B12") (pinfunction "B-12_B12") (pintype "passive"))
    )
    (net (code "87") (name "Net-(0X24-GPB4)") (class "Default")
      (node (ref "0X24") (pin "5") (pinfunction "GPB4_5") (pintype "bidirectional"))
      (node (ref "DIG5") (pin "B13") (pinfunction "B-13_B13") (pintype "passive"))
    )
    (net (code "88") (name "Net-(0X24-GPB5)") (class "Default")
      (node (ref "0X24") (pin "6") (pinfunction "GPB5_6") (pintype "bidirectional"))
      (node (ref "DIG5") (pin "B14") (pinfunction "B-14_B14") (pintype "passive"))
    )
    (net (code "89") (name "Net-(0X24-GPB6)") (class "Default")
      (node (ref "0X24") (pin "7") (pinfunction "GPB6_7") (pintype "bidirectional"))
      (node (ref "DIG5") (pin "B15") (pinfunction "B-15_B15") (pintype "passive"))
    )
    (net (code "90") (name "Net-(0X24-GPB7)") (class "Default")
      (node (ref "0X24") (pin "8") (pinfunction "GPB7_8") (pintype "bidirectional"))
      (node (ref "DIG5") (pin "B16") (pinfunction "B-16_B16") (pintype "passive"))
    )
    (net (code "91") (name "Net-(0X25-GPA0)") (class "Default")
      (node (ref "0X25") (pin "21") (pinfunction "GPA0_21") (pintype "bidirectional"))
      (node (ref "DIG6") (pin "B1") (pinfunction "B-1_B1") (pintype "passive"))
    )
    (net (code "92") (name "Net-(0X25-GPA1)") (class "Default")
      (node (ref "0X25") (pin "22") (pinfunction "GPA1_22") (pintype "bidirectional"))
      (node (ref "DIG6") (pin "B2") (pinfunction "B-2_B2") (pintype "passive"))
    )
    (net (code "93") (name "Net-(0X25-GPA2)") (class "Default")
      (node (ref "0X25") (pin "23") (pinfunction "GPA2_23") (pintype "bidirectional"))
      (node (ref "DIG6") (pin "B3") (pinfunction "B-3_B3") (pintype "passive"))
    )
    (net (code "94") (name "Net-(0X25-GPA3)") (class "Default")
      (node (ref "0X25") (pin "24") (pinfunction "GPA3_24") (pintype "bidirectional"))
      (node (ref "DIG6") (pin "B4") (pinfunction "B-4_B4") (pintype "passive"))
    )
    (net (code "95") (name "Net-(0X25-GPA4)") (class "Default")
      (node (ref "0X25") (pin "25") (pinfunction "GPA4_25") (pintype "bidirectional"))
      (node (ref "DIG6") (pin "B5") (pinfunction "B-5_B5") (pintype "passive"))
    )
    (net (code "96") (name "Net-(0X25-GPA5)") (class "Default")
      (node (ref "0X25") (pin "26") (pinfunction "GPA5_26") (pintype "bidirectional"))
      (node (ref "DIG6") (pin "B6") (pinfunction "B-6_B6") (pintype "passive"))
    )
    (net (code "97") (name "Net-(0X25-GPA6)") (class "Default")
      (node (ref "0X25") (pin "27") (pinfunction "GPA6_27") (pintype "bidirectional"))
      (node (ref "DIG6") (pin "B7") (pinfunction "B-7_B7") (pintype "passive"))
    )
    (net (code "98") (name "Net-(0X25-GPA7)") (class "Default")
      (node (ref "0X25") (pin "28") (pinfunction "GPA7_28") (pintype "bidirectional"))
      (node (ref "DIG6") (pin "B8") (pinfunction "B-8_B8") (pintype "passive"))
    )
    (net (code "99") (name "Net-(0X25-GPB0)") (class "Default")
      (node (ref "0X25") (pin "1") (pinfunction "GPB0_1") (pintype "bidirectional"))
      (node (ref "DIG6") (pin "B9") (pinfunction "B-9_B9") (pintype "passive"))
    )
    (net (code "100") (name "Net-(0X25-GPB1)") (class "Default")
      (node (ref "0X25") (pin "2") (pinfunction "GPB1_2") (pintype "bidirectional"))
      (node (ref "DIG6") (pin "B10") (pinfunction "B-10_B10") (pintype "passive"))
    )
    (net (code "101") (name "Net-(0X25-GPB2)") (class "Default")
      (node (ref "0X25") (pin "3") (pinfunction "GPB2_3") (pintype "bidirectional"))
      (node (ref "DIG6") (pin "B11") (pinfunction "B-11_B11") (pintype "passive"))
    )
    (net (code "102") (name "Net-(0X25-GPB3)") (class "Default")
      (node (ref "0X25") (pin "4") (pinfunction "GPB3_4") (pintype "bidirectional"))
      (node (ref "DIG6") (pin "B12") (pinfunction "B-12_B12") (pintype "passive"))
    )
    (net (code "103") (name "Net-(0X25-GPB4)") (class "Default")
      (node (ref "0X25") (pin "5") (pinfunction "GPB4_5") (pintype "bidirectional"))
      (node (ref "DIG6") (pin "B13") (pinfunction "B-13_B13") (pintype "passive"))
    )
    (net (code "104") (name "Net-(0X25-GPB5)") (class "Default")
      (node (ref "0X25") (pin "6") (pinfunction "GPB5_6") (pintype "bidirectional"))
      (node (ref "DIG6") (pin "B14") (pinfunction "B-14_B14") (pintype "passive"))
    )
    (net (code "105") (name "Net-(0X25-GPB6)") (class "Default")
      (node (ref "0X25") (pin "7") (pinfunction "GPB6_7") (pintype "bidirectional"))
      (node (ref "DIG6") (pin "B15") (pinfunction "B-15_B15") (pintype "passive"))
    )
    (net (code "106") (name "Net-(0X25-GPB7)") (class "Default")
      (node (ref "0X25") (pin "8") (pinfunction "GPB7_8") (pintype "bidirectional"))
      (node (ref "DIG6") (pin "B16") (pinfunction "B-16_B16") (pintype "passive"))
    )
    (net (code "107") (name "Net-(0X26-GPA0)") (class "Default")
      (node (ref "0X26") (pin "21") (pinfunction "GPA0_21") (pintype "bidirectional"))
      (node (ref "DIG7") (pin "B1") (pinfunction "B-1_B1") (pintype "passive"))
    )
    (net (code "108") (name "Net-(0X26-GPA1)") (class "Default")
      (node (ref "0X26") (pin "22") (pinfunction "GPA1_22") (pintype "bidirectional"))
      (node (ref "DIG7") (pin "B2") (pinfunction "B-2_B2") (pintype "passive"))
    )
    (net (code "109") (name "Net-(0X26-GPA2)") (class "Default")
      (node (ref "0X26") (pin "23") (pinfunction "GPA2_23") (pintype "bidirectional"))
      (node (ref "DIG7") (pin "B3") (pinfunction "B-3_B3") (pintype "passive"))
    )
    (net (code "110") (name "Net-(0X26-GPA3)") (class "Default")
      (node (ref "0X26") (pin "24") (pinfunction "GPA3_24") (pintype "bidirectional"))
      (node (ref "DIG7") (pin "B4") (pinfunction "B-4_B4") (pintype "passive"))
    )
    (net (code "111") (name "Net-(0X26-GPA4)") (class "Default")
      (node (ref "0X26") (pin "25") (pinfunction "GPA4_25") (pintype "bidirectional"))
      (node (ref "DIG7") (pin "B5") (pinfunction "B-5_B5") (pintype "passive"))
    )
    (net (code "112") (name "Net-(0X26-GPA5)") (class "Default")
      (node (ref "0X26") (pin "26") (pinfunction "GPA5_26") (pintype "bidirectional"))
      (node (ref "DIG7") (pin "B6") (pinfunction "B-6_B6") (pintype "passive"))
    )
    (net (code "113") (name "Net-(0X26-GPA6)") (class "Default")
      (node (ref "0X26") (pin "27") (pinfunction "GPA6_27") (pintype "bidirectional"))
      (node (ref "DIG7") (pin "B7") (pinfunction "B-7_B7") (pintype "passive"))
    )
    (net (code "114") (name "Net-(0X26-GPA7)") (class "Default")
      (node (ref "0X26") (pin "28") (pinfunction "GPA7_28") (pintype "bidirectional"))
      (node (ref "DIG7") (pin "B8") (pinfunction "B-8_B8") (pintype "passive"))
    )
    (net (code "115") (name "Net-(0X26-GPB0)") (class "Default")
      (node (ref "0X26") (pin "1") (pinfunction "GPB0_1") (pintype "bidirectional"))
      (node (ref "DIG7") (pin "B9") (pinfunction "B-9_B9") (pintype "passive"))
    )
    (net (code "116") (name "Net-(0X26-GPB1)") (class "Default")
      (node (ref "0X26") (pin "2") (pinfunction "GPB1_2") (pintype "bidirectional"))
      (node (ref "DIG7") (pin "B10") (pinfunction "B-10_B10") (pintype "passive"))
    )
    (net (code "117") (name "Net-(0X26-GPB2)") (class "Default")
      (node (ref "0X26") (pin "3") (pinfunction "GPB2_3") (pintype "bidirectional"))
      (node (ref "DIG7") (pin "B11") (pinfunction "B-11_B11") (pintype "passive"))
    )
    (net (code "118") (name "Net-(0X26-GPB3)") (class "Default")
      (node (ref "0X26") (pin "4") (pinfunction "GPB3_4") (pintype "bidirectional"))
      (node (ref "DIG7") (pin "B12") (pinfunction "B-12_B12") (pintype "passive"))
    )
    (net (code "119") (name "Net-(0X26-GPB4)") (class "Default")
      (node (ref "0X26") (pin "5") (pinfunction "GPB4_5") (pintype "bidirectional"))
      (node (ref "DIG7") (pin "B13") (pinfunction "B-13_B13") (pintype "passive"))
    )
    (net (code "120") (name "Net-(0X26-GPB5)") (class "Default")
      (node (ref "0X26") (pin "6") (pinfunction "GPB5_6") (pintype "bidirectional"))
      (node (ref "DIG7") (pin "B14") (pinfunction "B-14_B14") (pintype "passive"))
    )
    (net (code "121") (name "Net-(0X26-GPB6)") (class "Default")
      (node (ref "0X26") (pin "7") (pinfunction "GPB6_7") (pintype "bidirectional"))
      (node (ref "DIG7") (pin "B15") (pinfunction "B-15_B15") (pintype "passive"))
    )
    (net (code "122") (name "Net-(0X26-GPB7)") (class "Default")
      (node (ref "0X26") (pin "8") (pinfunction "GPB7_8") (pintype "bidirectional"))
      (node (ref "DIG7") (pin "B16") (pinfunction "B-16_B16") (pintype "passive"))
    )
    (net (code "123") (name "Net-(0X27-GPA0)") (class "Default")
      (node (ref "0X27") (pin "21") (pinfunction "GPA0_21") (pintype "bidirectional"))
      (node (ref "DIG8") (pin "B1") (pinfunction "B-1_B1") (pintype "passive"))
    )
    (net (code "124") (name "Net-(0X27-GPA1)") (class "Default")
      (node (ref "0X27") (pin "22") (pinfunction "GPA1_22") (pintype "bidirectional"))
      (node (ref "DIG8") (pin "B2") (pinfunction "B-2_B2") (pintype "passive"))
    )
    (net (code "125") (name "Net-(0X27-GPA2)") (class "Default")
      (node (ref "0X27") (pin "23") (pinfunction "GPA2_23") (pintype "bidirectional"))
      (node (ref "DIG8") (pin "B3") (pinfunction "B-3_B3") (pintype "passive"))
    )
    (net (code "126") (name "Net-(0X27-GPA3)") (class "Default")
      (node (ref "0X27") (pin "24") (pinfunction "GPA3_24") (pintype "bidirectional"))
      (node (ref "DIG8") (pin "B4") (pinfunction "B-4_B4") (pintype "passive"))
    )
    (net (code "127") (name "Net-(0X27-GPA4)") (class "Default")
      (node (ref "0X27") (pin "25") (pinfunction "GPA4_25") (pintype "bidirectional"))
      (node (ref "DIG8") (pin "B5") (pinfunction "B-5_B5") (pintype "passive"))
    )
    (net (code "128") (name "Net-(0X27-GPA5)") (class "Default")
      (node (ref "0X27") (pin "26") (pinfunction "GPA5_26") (pintype "bidirectional"))
      (node (ref "DIG8") (pin "B6") (pinfunction "B-6_B6") (pintype "passive"))
    )
    (net (code "129") (name "Net-(0X27-GPA6)") (class "Default")
      (node (ref "0X27") (pin "27") (pinfunction "GPA6_27") (pintype "bidirectional"))
      (node (ref "DIG8") (pin "B7") (pinfunction "B-7_B7") (pintype "passive"))
    )
    (net (code "130") (name "Net-(0X27-GPA7)") (class "Default")
      (node (ref "0X27") (pin "28") (pinfunction "GPA7_28") (pintype "bidirectional"))
      (node (ref "DIG8") (pin "B8") (pinfunction "B-8_B8") (pintype "passive"))
    )
    (net (code "131") (name "Net-(0X27-GPB0)") (class "Default")
      (node (ref "0X27") (pin "1") (pinfunction "GPB0_1") (pintype "bidirectional"))
      (node (ref "DIG8") (pin "B9") (pinfunction "B-9_B9") (pintype "passive"))
    )
    (net (code "132") (name "Net-(0X27-GPB1)") (class "Default")
      (node (ref "0X27") (pin "2") (pinfunction "GPB1_2") (pintype "bidirectional"))
      (node (ref "DIG8") (pin "B10") (pinfunction "B-10_B10") (pintype "passive"))
    )
    (net (code "133") (name "Net-(0X27-GPB2)") (class "Default")
      (node (ref "0X27") (pin "3") (pinfunction "GPB2_3") (pintype "bidirectional"))
      (node (ref "DIG8") (pin "B11") (pinfunction "B-11_B11") (pintype "passive"))
    )
    (net (code "134") (name "Net-(0X27-GPB3)") (class "Default")
      (node (ref "0X27") (pin "4") (pinfunction "GPB3_4") (pintype "bidirectional"))
      (node (ref "DIG8") (pin "B12") (pinfunction "B-12_B12") (pintype "passive"))
    )
    (net (code "135") (name "Net-(0X27-GPB4)") (class "Default")
      (node (ref "0X27") (pin "5") (pinfunction "GPB4_5") (pintype "bidirectional"))
      (node (ref "DIG8") (pin "B13") (pinfunction "B-13_B13") (pintype "passive"))
    )
    (net (code "136") (name "Net-(0X27-GPB5)") (class "Default")
      (node (ref "0X27") (pin "6") (pinfunction "GPB5_6") (pintype "bidirectional"))
      (node (ref "DIG8") (pin "B14") (pinfunction "B-14_B14") (pintype "passive"))
    )
    (net (code "137") (name "Net-(0X27-GPB6)") (class "Default")
      (node (ref "0X27") (pin "7") (pinfunction "GPB6_7") (pintype "bidirectional"))
      (node (ref "DIG8") (pin "B15") (pinfunction "B-15_B15") (pintype "passive"))
    )
    (net (code "138") (name "Net-(0X27-GPB7)") (class "Default")
      (node (ref "0X27") (pin "8") (pinfunction "GPB7_8") (pintype "bidirectional"))
      (node (ref "DIG8") (pin "B16") (pinfunction "B-16_B16") (pintype "passive"))
    )
    (net (code "139") (name "Net-(ANALOG-B-1)") (class "Default")
      (node (ref "ANALOG") (pin "B1") (pinfunction "B-1_B1") (pintype "passive"))
      (node (ref "MCP3008-CS1") (pin "8") (pinfunction "CH7_8") (pintype "input"))
    )
    (net (code "140") (name "Net-(ANALOG-B-2)") (class "Default")
      (node (ref "ANALOG") (pin "B2") (pinfunction "B-2_B2") (pintype "passive"))
      (node (ref "MCP3008-CS1") (pin "7") (pinfunction "CH6_7") (pintype "input"))
    )
    (net (code "141") (name "Net-(ANALOG-B-3)") (class "Default")
      (node (ref "ANALOG") (pin "B3") (pinfunction "B-3_B3") (pintype "passive"))
      (node (ref "MCP3008-CS1") (pin "6") (pinfunction "CH5_6") (pintype "input"))
    )
    (net (code "142") (name "Net-(ANALOG-B-4)") (class "Default")
      (node (ref "ANALOG") (pin "B4") (pinfunction "B-4_B4") (pintype "passive"))
      (node (ref "MCP3008-CS1") (pin "5") (pinfunction "CH4_5") (pintype "input"))
    )
    (net (code "143") (name "Net-(ANALOG-B-5)") (class "Default")
      (node (ref "ANALOG") (pin "B5") (pinfunction "B-5_B5") (pintype "passive"))
      (node (ref "MCP3008-CS1") (pin "4") (pinfunction "CH3_4") (pintype "input"))
    )
    (net (code "144") (name "Net-(ANALOG-B-6)") (class "Default")
      (node (ref "ANALOG") (pin "B6") (pinfunction "B-6_B6") (pintype "passive"))
      (node (ref "MCP3008-CS1") (pin "3") (pinfunction "CH2_3") (pintype "input"))
    )
    (net (code "145") (name "Net-(ANALOG-B-7)") (class "Default")
      (node (ref "ANALOG") (pin "B7") (pinfunction "B-7_B7") (pintype "passive"))
      (node (ref "MCP3008-CS1") (pin "2") (pinfunction "CH1_2") (pintype "input"))
    )
    (net (code "146") (name "Net-(ANALOG-B-8)") (class "Default")
      (node (ref "ANALOG") (pin "B8") (pinfunction "B-8_B8") (pintype "passive"))
      (node (ref "MCP3008-CS1") (pin "1") (pinfunction "CH0_1") (pintype "input"))
    )
    (net (code "147") (name "Net-(ANALOG-B-9)") (class "Default")
      (node (ref "ANALOG") (pin "B9") (pinfunction "B-9_B9") (pintype "passive"))
      (node (ref "MCP3008-CS0") (pin "8") (pinfunction "CH7_8") (pintype "input"))
    )
    (net (code "148") (name "Net-(ANALOG-B-10)") (class "Default")
      (node (ref "ANALOG") (pin "B10") (pinfunction "B-10_B10") (pintype "passive"))
      (node (ref "MCP3008-CS0") (pin "7") (pinfunction "CH6_7") (pintype "input"))
    )
    (net (code "149") (name "Net-(ANALOG-B-11)") (class "Default")
      (node (ref "ANALOG") (pin "B11") (pinfunction "B-11_B11") (pintype "passive"))
      (node (ref "MCP3008-CS0") (pin "6") (pinfunction "CH5_6") (pintype "input"))
    )
    (net (code "150") (name "Net-(ANALOG-B-12)") (class "Default")
      (node (ref "ANALOG") (pin "B12") (pinfunction "B-12_B12") (pintype "passive"))
      (node (ref "MCP3008-CS0") (pin "5") (pinfunction "CH4_5") (pintype "input"))
    )
    (net (code "151") (name "Net-(ANALOG-B-13)") (class "Default")
      (node (ref "ANALOG") (pin "B13") (pinfunction "B-13_B13") (pintype "passive"))
      (node (ref "MCP3008-CS0") (pin "4") (pinfunction "CH3_4") (pintype "input"))
    )
    (net (code "152") (name "Net-(ANALOG-B-14)") (class "Default")
      (node (ref "ANALOG") (pin "B14") (pinfunction "B-14_B14") (pintype "passive"))
      (node (ref "MCP3008-CS0") (pin "3") (pinfunction "CH2_3") (pintype "input"))
    )
    (net (code "153") (name "Net-(ANALOG-B-15)") (class "Default")
      (node (ref "ANALOG") (pin "B15") (pinfunction "B-15_B15") (pintype "passive"))
      (node (ref "MCP3008-CS0") (pin "2") (pinfunction "CH1_2") (pintype "input"))
    )
    (net (code "154") (name "Net-(ANALOG-B-16)") (class "Default")
      (node (ref "ANALOG") (pin "B16") (pinfunction "B-16_B16") (pintype "passive"))
      (node (ref "MCP3008-CS0") (pin "1") (pinfunction "CH0_1") (pintype "input"))
    )
    (net (code "155") (name "unconnected-(0X20-INTA-Pad20)") (class "Default")
      (node (ref "0X20") (pin "20") (pinfunction "INTA_20") (pintype "output"))
    )
    (net (code "156") (name "unconnected-(0X20-INTB-Pad19)") (class "Default")
      (node (ref "0X20") (pin "19") (pinfunction "INTB_19") (pintype "output"))
    )
    (net (code "157") (name "unconnected-(0X21-INTA-Pad20)") (class "Default")
      (node (ref "0X21") (pin "20") (pinfunction "INTA_20") (pintype "output"))
    )
    (net (code "158") (name "unconnected-(0X21-INTB-Pad19)") (class "Default")
      (node (ref "0X21") (pin "19") (pinfunction "INTB_19") (pintype "output"))
    )
    (net (code "159") (name "unconnected-(0X22-INTA-Pad20)") (class "Default")
      (node (ref "0X22") (pin "20") (pinfunction "INTA_20") (pintype "output"))
    )
    (net (code "160") (name "unconnected-(0X22-INTB-Pad19)") (class "Default")
      (node (ref "0X22") (pin "19") (pinfunction "INTB_19") (pintype "output"))
    )
    (net (code "161") (name "unconnected-(0X23-INTA-Pad20)") (class "Default")
      (node (ref "0X23") (pin "20") (pinfunction "INTA_20") (pintype "output"))
    )
    (net (code "162") (name "unconnected-(0X23-INTB-Pad19)") (class "Default")
      (node (ref "0X23") (pin "19") (pinfunction "INTB_19") (pintype "output"))
    )
    (net (code "163") (name "unconnected-(0X24-INTA-Pad20)") (class "Default")
      (node (ref "0X24") (pin "20") (pinfunction "INTA_20") (pintype "output"))
    )
    (net (code "164") (name "unconnected-(0X24-INTB-Pad19)") (class "Default")
      (node (ref "0X24") (pin "19") (pinfunction "INTB_19") (pintype "output"))
    )
    (net (code "165") (name "unconnected-(0X25-INTA-Pad20)") (class "Default")
      (node (ref "0X25") (pin "20") (pinfunction "INTA_20") (pintype "output"))
    )
    (net (code "166") (name "unconnected-(0X25-INTB-Pad19)") (class "Default")
      (node (ref "0X25") (pin "19") (pinfunction "INTB_19") (pintype "output"))
    )
    (net (code "167") (name "unconnected-(0X26-INTA-Pad20)") (class "Default")
      (node (ref "0X26") (pin "20") (pinfunction "INTA_20") (pintype "output"))
    )
    (net (code "168") (name "unconnected-(0X26-INTB-Pad19)") (class "Default")
      (node (ref "0X26") (pin "19") (pinfunction "INTB_19") (pintype "output"))
    )
    (net (code "169") (name "unconnected-(0X27-INTA-Pad20)") (class "Default")
      (node (ref "0X27") (pin "20") (pinfunction "INTA_20") (pintype "output"))
    )
    (net (code "170") (name "unconnected-(0X27-INTB-Pad19)") (class "Default")
      (node (ref "0X27") (pin "19") (pinfunction "INTB_19") (pintype "output"))
    )
    (net (code "171") (name "unconnected-(ANALOG--1-PadA1)") (class "Default")
      (node (ref "ANALOG") (pin "A1") (pinfunction "-1_A1") (pintype "passive"))
    )
    (net (code "172") (name "unconnected-(ANALOG--2-PadA2)") (class "Default")
      (node (ref "ANALOG") (pin "A2") (pinfunction "-2_A2") (pintype "passive"))
    )
    (net (code "173") (name "unconnected-(ANALOG--3-PadA3)") (class "Default")
      (node (ref "ANALOG") (pin "A3") (pinfunction "-3_A3") (pintype "passive"))
    )
    (net (code "174") (name "unconnected-(ANALOG--4-PadA4)") (class "Default")
      (node (ref "ANALOG") (pin "A4") (pinfunction "-4_A4") (pintype "passive"))
    )
    (net (code "175") (name "unconnected-(ANALOG--5-PadA5)") (class "Default")
      (node (ref "ANALOG") (pin "A5") (pinfunction "-5_A5") (pintype "passive"))
    )
    (net (code "176") (name "unconnected-(ANALOG--6-PadA6)") (class "Default")
      (node (ref "ANALOG") (pin "A6") (pinfunction "-6_A6") (pintype "passive"))
    )
    (net (code "177") (name "unconnected-(ANALOG--7-PadA7)") (class "Default")
      (node (ref "ANALOG") (pin "A7") (pinfunction "-7_A7") (pintype "passive"))
    )
    (net (code "178") (name "unconnected-(ANALOG--8-PadA8)") (class "Default")
      (node (ref "ANALOG") (pin "A8") (pinfunction "-8_A8") (pintype "passive"))
    )
    (net (code "179") (name "unconnected-(ANALOG--9-PadA9)") (class "Default")
      (node (ref "ANALOG") (pin "A9") (pinfunction "-9_A9") (pintype "passive"))
    )
    (net (code "180") (name "unconnected-(ANALOG--10-PadA10)") (class "Default")
      (node (ref "ANALOG") (pin "A10") (pinfunction "-10_A10") (pintype "passive"))
    )
    (net (code "181") (name "unconnected-(ANALOG--11-PadA11)") (class "Default")
      (node (ref "ANALOG") (pin "A11") (pinfunction "-11_A11") (pintype "passive"))
    )
    (net (code "182") (name "unconnected-(ANALOG--12-PadA12)") (class "Default")
      (node (ref "ANALOG") (pin "A12") (pinfunction "-12_A12") (pintype "passive"))
    )
    (net (code "183") (name "unconnected-(ANALOG--13-PadA13)") (class "Default")
      (node (ref "ANALOG") (pin "A13") (pinfunction "-13_A13") (pintype "passive"))
    )
    (net (code "184") (name "unconnected-(ANALOG--14-PadA14)") (class "Default")
      (node (ref "ANALOG") (pin "A14") (pinfunction "-14_A14") (pintype "passive"))
    )
    (net (code "185") (name "unconnected-(ANALOG--15-PadA15)") (class "Default")
      (node (ref "ANALOG") (pin "A15") (pinfunction "-15_A15") (pintype "passive"))
    )
    (net (code "186") (name "unconnected-(ANALOG--16-PadA16)") (class "Default")
      (node (ref "ANALOG") (pin "A16") (pinfunction "-16_A16") (pintype "passive"))
    )
    (net (code "187") (name "unconnected-(DIG1--1-PadA1)") (class "Default")
      (node (ref "DIG1") (pin "A1") (pinfunction "-1_A1") (pintype "passive"))
    )
    (net (code "188") (name "unconnected-(DIG1--2-PadA2)") (class "Default")
      (node (ref "DIG1") (pin "A2") (pinfunction "-2_A2") (pintype "passive"))
    )
    (net (code "189") (name "unconnected-(DIG1--3-PadA3)") (class "Default")
      (node (ref "DIG1") (pin "A3") (pinfunction "-3_A3") (pintype "passive"))
    )
    (net (code "190") (name "unconnected-(DIG1--4-PadA4)") (class "Default")
      (node (ref "DIG1") (pin "A4") (pinfunction "-4_A4") (pintype "passive"))
    )
    (net (code "191") (name "unconnected-(DIG1--5-PadA5)") (class "Default")
      (node (ref "DIG1") (pin "A5") (pinfunction "-5_A5") (pintype "passive"))
    )
    (net (code "192") (name "unconnected-(DIG1--6-PadA6)") (class "Default")
      (node (ref "DIG1") (pin "A6") (pinfunction "-6_A6") (pintype "passive"))
    )
    (net (code "193") (name "unconnected-(DIG1--7-PadA7)") (class "Default")
      (node (ref "DIG1") (pin "A7") (pinfunction "-7_A7") (pintype "passive"))
    )
    (net (code "194") (name "unconnected-(DIG1--8-PadA8)") (class "Default")
      (node (ref "DIG1") (pin "A8") (pinfunction "-8_A8") (pintype "passive"))
    )
    (net (code "195") (name "unconnected-(DIG1--9-PadA9)") (class "Default")
      (node (ref "DIG1") (pin "A9") (pinfunction "-9_A9") (pintype "passive"))
    )
    (net (code "196") (name "unconnected-(DIG1--10-PadA10)") (class "Default")
      (node (ref "DIG1") (pin "A10") (pinfunction "-10_A10") (pintype "passive"))
    )
    (net (code "197") (name "unconnected-(DIG1--11-PadA11)") (class "Default")
      (node (ref "DIG1") (pin "A11") (pinfunction "-11_A11") (pintype "passive"))
    )
    (net (code "198") (name "unconnected-(DIG1--12-PadA12)") (class "Default")
      (node (ref "DIG1") (pin "A12") (pinfunction "-12_A12") (pintype "passive"))
    )
    (net (code "199") (name "unconnected-(DIG1--13-PadA13)") (class "Default")
      (node (ref "DIG1") (pin "A13") (pinfunction "-13_A13") (pintype "passive"))
    )
    (net (code "200") (name "unconnected-(DIG1--14-PadA14)") (class "Default")
      (node (ref "DIG1") (pin "A14") (pinfunction "-14_A14") (pintype "passive"))
    )
    (net (code "201") (name "unconnected-(DIG1--15-PadA15)") (class "Default")
      (node (ref "DIG1") (pin "A15") (pinfunction "-15_A15") (pintype "passive"))
    )
    (net (code "202") (name "unconnected-(DIG1--16-PadA16)") (class "Default")
      (node (ref "DIG1") (pin "A16") (pinfunction "-16_A16") (pintype "passive"))
    )
    (net (code "203") (name "unconnected-(DIG2--1-PadA1)") (class "Default")
      (node (ref "DIG2") (pin "A1") (pinfunction "-1_A1") (pintype "passive"))
    )
    (net (code "204") (name "unconnected-(DIG2--2-PadA2)") (class "Default")
      (node (ref "DIG2") (pin "A2") (pinfunction "-2_A2") (pintype "passive"))
    )
    (net (code "205") (name "unconnected-(DIG2--3-PadA3)") (class "Default")
      (node (ref "DIG2") (pin "A3") (pinfunction "-3_A3") (pintype "passive"))
    )
    (net (code "206") (name "unconnected-(DIG2--4-PadA4)") (class "Default")
      (node (ref "DIG2") (pin "A4") (pinfunction "-4_A4") (pintype "passive"))
    )
    (net (code "207") (name "unconnected-(DIG2--5-PadA5)") (class "Default")
      (node (ref "DIG2") (pin "A5") (pinfunction "-5_A5") (pintype "passive"))
    )
    (net (code "208") (name "unconnected-(DIG2--6-PadA6)") (class "Default")
      (node (ref "DIG2") (pin "A6") (pinfunction "-6_A6") (pintype "passive"))
    )
    (net (code "209") (name "unconnected-(DIG2--7-PadA7)") (class "Default")
      (node (ref "DIG2") (pin "A7") (pinfunction "-7_A7") (pintype "passive"))
    )
    (net (code "210") (name "unconnected-(DIG2--8-PadA8)") (class "Default")
      (node (ref "DIG2") (pin "A8") (pinfunction "-8_A8") (pintype "passive"))
    )
    (net (code "211") (name "unconnected-(DIG2--9-PadA9)") (class "Default")
      (node (ref "DIG2") (pin "A9") (pinfunction "-9_A9") (pintype "passive"))
    )
    (net (code "212") (name "unconnected-(DIG2--10-PadA10)") (class "Default")
      (node (ref "DIG2") (pin "A10") (pinfunction "-10_A10") (pintype "passive"))
    )
    (net (code "213") (name "unconnected-(DIG2--11-PadA11)") (class "Default")
      (node (ref "DIG2") (pin "A11") (pinfunction "-11_A11") (pintype "passive"))
    )
    (net (code "214") (name "unconnected-(DIG2--12-PadA12)") (class "Default")
      (node (ref "DIG2") (pin "A12") (pinfunction "-12_A12") (pintype "passive"))
    )
    (net (code "215") (name "unconnected-(DIG2--13-PadA13)") (class "Default")
      (node (ref "DIG2") (pin "A13") (pinfunction "-13_A13") (pintype "passive"))
    )
    (net (code "216") (name "unconnected-(DIG2--14-PadA14)") (class "Default")
      (node (ref "DIG2") (pin "A14") (pinfunction "-14_A14") (pintype "passive"))
    )
    (net (code "217") (name "unconnected-(DIG2--15-PadA15)") (class "Default")
      (node (ref "DIG2") (pin "A15") (pinfunction "-15_A15") (pintype "passive"))
    )
    (net (code "218") (name "unconnected-(DIG2--16-PadA16)") (class "Default")
      (node (ref "DIG2") (pin "A16") (pinfunction "-16_A16") (pintype "passive"))
    )
    (net (code "219") (name "unconnected-(DIG3--1-PadA1)") (class "Default")
      (node (ref "DIG3") (pin "A1") (pinfunction "-1_A1") (pintype "passive"))
    )
    (net (code "220") (name "unconnected-(DIG3--2-PadA2)") (class "Default")
      (node (ref "DIG3") (pin "A2") (pinfunction "-2_A2") (pintype "passive"))
    )
    (net (code "221") (name "unconnected-(DIG3--3-PadA3)") (class "Default")
      (node (ref "DIG3") (pin "A3") (pinfunction "-3_A3") (pintype "passive"))
    )
    (net (code "222") (name "unconnected-(DIG3--4-PadA4)") (class "Default")
      (node (ref "DIG3") (pin "A4") (pinfunction "-4_A4") (pintype "passive"))
    )
    (net (code "223") (name "unconnected-(DIG3--5-PadA5)") (class "Default")
      (node (ref "DIG3") (pin "A5") (pinfunction "-5_A5") (pintype "passive"))
    )
    (net (code "224") (name "unconnected-(DIG3--6-PadA6)") (class "Default")
      (node (ref "DIG3") (pin "A6") (pinfunction "-6_A6") (pintype "passive"))
    )
    (net (code "225") (name "unconnected-(DIG3--7-PadA7)") (class "Default")
      (node (ref "DIG3") (pin "A7") (pinfunction "-7_A7") (pintype "passive"))
    )
    (net (code "226") (name "unconnected-(DIG3--8-PadA8)") (class "Default")
      (node (ref "DIG3") (pin "A8") (pinfunction "-8_A8") (pintype "passive"))
    )
    (net (code "227") (name "unconnected-(DIG3--9-PadA9)") (class "Default")
      (node (ref "DIG3") (pin "A9") (pinfunction "-9_A9") (pintype "passive"))
    )
    (net (code "228") (name "unconnected-(DIG3--10-PadA10)") (class "Default")
      (node (ref "DIG3") (pin "A10") (pinfunction "-10_A10") (pintype "passive"))
    )
    (net (code "229") (name "unconnected-(DIG3--11-PadA11)") (class "Default")
      (node (ref "DIG3") (pin "A11") (pinfunction "-11_A11") (pintype "passive"))
    )
    (net (code "230") (name "unconnected-(DIG3--12-PadA12)") (class "Default")
      (node (ref "DIG3") (pin "A12") (pinfunction "-12_A12") (pintype "passive"))
    )
    (net (code "231") (name "unconnected-(DIG3--13-PadA13)") (class "Default")
      (node (ref "DIG3") (pin "A13") (pinfunction "-13_A13") (pintype "passive"))
    )
    (net (code "232") (name "unconnected-(DIG3--14-PadA14)") (class "Default")
      (node (ref "DIG3") (pin "A14") (pinfunction "-14_A14") (pintype "passive"))
    )
    (net (code "233") (name "unconnected-(DIG3--15-PadA15)") (class "Default")
      (node (ref "DIG3") (pin "A15") (pinfunction "-15_A15") (pintype "passive"))
    )
    (net (code "234") (name "unconnected-(DIG3--16-PadA16)") (class "Default")
      (node (ref "DIG3") (pin "A16") (pinfunction "-16_A16") (pintype "passive"))
    )
    (net (code "235") (name "unconnected-(DIG4--1-PadA1)") (class "Default")
      (node (ref "DIG4") (pin "A1") (pinfunction "-1_A1") (pintype "passive"))
    )
    (net (code "236") (name "unconnected-(DIG4--2-PadA2)") (class "Default")
      (node (ref "DIG4") (pin "A2") (pinfunction "-2_A2") (pintype "passive"))
    )
    (net (code "237") (name "unconnected-(DIG4--3-PadA3)") (class "Default")
      (node (ref "DIG4") (pin "A3") (pinfunction "-3_A3") (pintype "passive"))
    )
    (net (code "238") (name "unconnected-(DIG4--4-PadA4)") (class "Default")
      (node (ref "DIG4") (pin "A4") (pinfunction "-4_A4") (pintype "passive"))
    )
    (net (code "239") (name "unconnected-(DIG4--5-PadA5)") (class "Default")
      (node (ref "DIG4") (pin "A5") (pinfunction "-5_A5") (pintype "passive"))
    )
    (net (code "240") (name "unconnected-(DIG4--6-PadA6)") (class "Default")
      (node (ref "DIG4") (pin "A6") (pinfunction "-6_A6") (pintype "passive"))
    )
    (net (code "241") (name "unconnected-(DIG4--7-PadA7)") (class "Default")
      (node (ref "DIG4") (pin "A7") (pinfunction "-7_A7") (pintype "passive"))
    )
    (net (code "242") (name "unconnected-(DIG4--8-PadA8)") (class "Default")
      (node (ref "DIG4") (pin "A8") (pinfunction "-8_A8") (pintype "passive"))
    )
    (net (code "243") (name "unconnected-(DIG4--9-PadA9)") (class "Default")
      (node (ref "DIG4") (pin "A9") (pinfunction "-9_A9") (pintype "passive"))
    )
    (net (code "244") (name "unconnected-(DIG4--10-PadA10)") (class "Default")
      (node (ref "DIG4") (pin "A10") (pinfunction "-10_A10") (pintype "passive"))
    )
    (net (code "245") (name "unconnected-(DIG4--11-PadA11)") (class "Default")
      (node (ref "DIG4") (pin "A11") (pinfunction "-11_A11") (pintype "passive"))
    )
    (net (code "246") (name "unconnected-(DIG4--12-PadA12)") (class "Default")
      (node (ref "DIG4") (pin "A12") (pinfunction "-12_A12") (pintype "passive"))
    )
    (net (code "247") (name "unconnected-(DIG4--13-PadA13)") (class "Default")
      (node (ref "DIG4") (pin "A13") (pinfunction "-13_A13") (pintype "passive"))
    )
    (net (code "248") (name "unconnected-(DIG4--14-PadA14)") (class "Default")
      (node (ref "DIG4") (pin "A14") (pinfunction "-14_A14") (pintype "passive"))
    )
    (net (code "249") (name "unconnected-(DIG4--15-PadA15)") (class "Default")
      (node (ref "DIG4") (pin "A15") (pinfunction "-15_A15") (pintype "passive"))
    )
    (net (code "250") (name "unconnected-(DIG4--16-PadA16)") (class "Default")
      (node (ref "DIG4") (pin "A16") (pinfunction "-16_A16") (pintype "passive"))
    )
    (net (code "251") (name "unconnected-(DIG5--1-PadA1)") (class "Default")
      (node (ref "DIG5") (pin "A1") (pinfunction "-1_A1") (pintype "passive"))
    )
    (net (code "252") (name "unconnected-(DIG5--2-PadA2)") (class "Default")
      (node (ref "DIG5") (pin "A2") (pinfunction "-2_A2") (pintype "passive"))
    )
    (net (code "253") (name "unconnected-(DIG5--3-PadA3)") (class "Default")
      (node (ref "DIG5") (pin "A3") (pinfunction "-3_A3") (pintype "passive"))
    )
    (net (code "254") (name "unconnected-(DIG5--4-PadA4)") (class "Default")
      (node (ref "DIG5") (pin "A4") (pinfunction "-4_A4") (pintype "passive"))
    )
    (net (code "255") (name "unconnected-(DIG5--5-PadA5)") (class "Default")
      (node (ref "DIG5") (pin "A5") (pinfunction "-5_A5") (pintype "passive"))
    )
    (net (code "256") (name "unconnected-(DIG5--6-PadA6)") (class "Default")
      (node (ref "DIG5") (pin "A6") (pinfunction "-6_A6") (pintype "passive"))
    )
    (net (code "257") (name "unconnected-(DIG5--7-PadA7)") (class "Default")
      (node (ref "DIG5") (pin "A7") (pinfunction "-7_A7") (pintype "passive"))
    )
    (net (code "258") (name "unconnected-(DIG5--8-PadA8)") (class "Default")
      (node (ref "DIG5") (pin "A8") (pinfunction "-8_A8") (pintype "passive"))
    )
    (net (code "259") (name "unconnected-(DIG5--9-PadA9)") (class "Default")
      (node (ref "DIG5") (pin "A9") (pinfunction "-9_A9") (pintype "passive"))
    )
    (net (code "260") (name "unconnected-(DIG5--10-PadA10)") (class "Default")
      (node (ref "DIG5") (pin "A10") (pinfunction "-10_A10") (pintype "passive"))
    )
    (net (code "261") (name "unconnected-(DIG5--11-PadA11)") (class "Default")
      (node (ref "DIG5") (pin "A11") (pinfunction "-11_A11") (pintype "passive"))
    )
    (net (code "262") (name "unconnected-(DIG5--12-PadA12)") (class "Default")
      (node (ref "DIG5") (pin "A12") (pinfunction "-12_A12") (pintype "passive"))
    )
    (net (code "263") (name "unconnected-(DIG5--13-PadA13)") (class "Default")
      (node (ref "DIG5") (pin "A13") (pinfunction "-13_A13") (pintype "passive"))
    )
    (net (code "264") (name "unconnected-(DIG5--14-PadA14)") (class "Default")
      (node (ref "DIG5") (pin "A14") (pinfunction "-14_A14") (pintype "passive"))
    )
    (net (code "265") (name "unconnected-(DIG5--15-PadA15)") (class "Default")
      (node (ref "DIG5") (pin "A15") (pinfunction "-15_A15") (pintype "passive"))
    )
    (net (code "266") (name "unconnected-(DIG5--16-PadA16)") (class "Default")
      (node (ref "DIG5") (pin "A16") (pinfunction "-16_A16") (pintype "passive"))
    )
    (net (code "267") (name "unconnected-(DIG6--1-PadA1)") (class "Default")
      (node (ref "DIG6") (pin "A1") (pinfunction "-1_A1") (pintype "passive"))
    )
    (net (code "268") (name "unconnected-(DIG6--2-PadA2)") (class "Default")
      (node (ref "DIG6") (pin "A2") (pinfunction "-2_A2") (pintype "passive"))
    )
    (net (code "269") (name "unconnected-(DIG6--3-PadA3)") (class "Default")
      (node (ref "DIG6") (pin "A3") (pinfunction "-3_A3") (pintype "passive"))
    )
    (net (code "270") (name "unconnected-(DIG6--4-PadA4)") (class "Default")
      (node (ref "DIG6") (pin "A4") (pinfunction "-4_A4") (pintype "passive"))
    )
    (net (code "271") (name "unconnected-(DIG6--5-PadA5)") (class "Default")
      (node (ref "DIG6") (pin "A5") (pinfunction "-5_A5") (pintype "passive"))
    )
    (net (code "272") (name "unconnected-(DIG6--6-PadA6)") (class "Default")
      (node (ref "DIG6") (pin "A6") (pinfunction "-6_A6") (pintype "passive"))
    )
    (net (code "273") (name "unconnected-(DIG6--7-PadA7)") (class "Default")
      (node (ref "DIG6") (pin "A7") (pinfunction "-7_A7") (pintype "passive"))
    )
    (net (code "274") (name "unconnected-(DIG6--8-PadA8)") (class "Default")
      (node (ref "DIG6") (pin "A8") (pinfunction "-8_A8") (pintype "passive"))
    )
    (net (code "275") (name "unconnected-(DIG6--9-PadA9)") (class "Default")
      (node (ref "DIG6") (pin "A9") (pinfunction "-9_A9") (pintype "passive"))
    )
    (net (code "276") (name "unconnected-(DIG6--10-PadA10)") (class "Default")
      (node (ref "DIG6") (pin "A10") (pinfunction "-10_A10") (pintype "passive"))
    )
    (net (code "277") (name "unconnected-(DIG6--11-PadA11)") (class "Default")
      (node (ref "DIG6") (pin "A11") (pinfunction "-11_A11") (pintype "passive"))
    )
    (net (code "278") (name "unconnected-(DIG6--12-PadA12)") (class "Default")
      (node (ref "DIG6") (pin "A12") (pinfunction "-12_A12") (pintype "passive"))
    )
    (net (code "279") (name "unconnected-(DIG6--13-PadA13)") (class "Default")
      (node (ref "DIG6") (pin "A13") (pinfunction "-13_A13") (pintype "passive"))
    )
    (net (code "280") (name "unconnected-(DIG6--14-PadA14)") (class "Default")
      (node (ref "DIG6") (pin "A14") (pinfunction "-14_A14") (pintype "passive"))
    )
    (net (code "281") (name "unconnected-(DIG6--15-PadA15)") (class "Default")
      (node (ref "DIG6") (pin "A15") (pinfunction "-15_A15") (pintype "passive"))
    )
    (net (code "282") (name "unconnected-(DIG6--16-PadA16)") (class "Default")
      (node (ref "DIG6") (pin "A16") (pinfunction "-16_A16") (pintype "passive"))
    )
    (net (code "283") (name "unconnected-(DIG7--1-PadA1)") (class "Default")
      (node (ref "DIG7") (pin "A1") (pinfunction "-1_A1") (pintype "passive"))
    )
    (net (code "284") (name "unconnected-(DIG7--2-PadA2)") (class "Default")
      (node (ref "DIG7") (pin "A2") (pinfunction "-2_A2") (pintype "passive"))
    )
    (net (code "285") (name "unconnected-(DIG7--3-PadA3)") (class "Default")
      (node (ref "DIG7") (pin "A3") (pinfunction "-3_A3") (pintype "passive"))
    )
    (net (code "286") (name "unconnected-(DIG7--4-PadA4)") (class "Default")
      (node (ref "DIG7") (pin "A4") (pinfunction "-4_A4") (pintype "passive"))
    )
    (net (code "287") (name "unconnected-(DIG7--5-PadA5)") (class "Default")
      (node (ref "DIG7") (pin "A5") (pinfunction "-5_A5") (pintype "passive"))
    )
    (net (code "288") (name "unconnected-(DIG7--6-PadA6)") (class "Default")
      (node (ref "DIG7") (pin "A6") (pinfunction "-6_A6") (pintype "passive"))
    )
    (net (code "289") (name "unconnected-(DIG7--7-PadA7)") (class "Default")
      (node (ref "DIG7") (pin "A7") (pinfunction "-7_A7") (pintype "passive"))
    )
    (net (code "290") (name "unconnected-(DIG7--8-PadA8)") (class "Default")
      (node (ref "DIG7") (pin "A8") (pinfunction "-8_A8") (pintype "passive"))
    )
    (net (code "291") (name "unconnected-(DIG7--9-PadA9)") (class "Default")
      (node (ref "DIG7") (pin "A9") (pinfunction "-9_A9") (pintype "passive"))
    )
    (net (code "292") (name "unconnected-(DIG7--10-PadA10)") (class "Default")
      (node (ref "DIG7") (pin "A10") (pinfunction "-10_A10") (pintype "passive"))
    )
    (net (code "293") (name "unconnected-(DIG7--11-PadA11)") (class "Default")
      (node (ref "DIG7") (pin "A11") (pinfunction "-11_A11") (pintype "passive"))
    )
    (net (code "294") (name "unconnected-(DIG7--12-PadA12)") (class "Default")
      (node (ref "DIG7") (pin "A12") (pinfunction "-12_A12") (pintype "passive"))
    )
    (net (code "295") (name "unconnected-(DIG7--13-PadA13)") (class "Default")
      (node (ref "DIG7") (pin "A13") (pinfunction "-13_A13") (pintype "passive"))
    )
    (net (code "296") (name "unconnected-(DIG7--14-PadA14)") (class "Default")
      (node (ref "DIG7") (pin "A14") (pinfunction "-14_A14") (pintype "passive"))
    )
    (net (code "297") (name "unconnected-(DIG7--15-PadA15)") (class "Default")
      (node (ref "DIG7") (pin "A15") (pinfunction "-15_A15") (pintype "passive"))
    )
    (net (code "298") (name "unconnected-(DIG7--16-PadA16)") (class "Default")
      (node (ref "DIG7") (pin "A16") (pinfunction "-16_A16") (pintype "passive"))
    )
    (net (code "299") (name "unconnected-(DIG8--1-PadA1)") (class "Default")
      (node (ref "DIG8") (pin "A1") (pinfunction "-1_A1") (pintype "passive"))
    )
    (net (code "300") (name "unconnected-(DIG8--2-PadA2)") (class "Default")
      (node (ref "DIG8") (pin "A2") (pinfunction "-2_A2") (pintype "passive"))
    )
    (net (code "301") (name "unconnected-(DIG8--3-PadA3)") (class "Default")
      (node (ref "DIG8") (pin "A3") (pinfunction "-3_A3") (pintype "passive"))
    )
    (net (code "302") (name "unconnected-(DIG8--4-PadA4)") (class "Default")
      (node (ref "DIG8") (pin "A4") (pinfunction "-4_A4") (pintype "passive"))
    )
    (net (code "303") (name "unconnected-(DIG8--5-PadA5)") (class "Default")
      (node (ref "DIG8") (pin "A5") (pinfunction "-5_A5") (pintype "passive"))
    )
    (net (code "304") (name "unconnected-(DIG8--6-PadA6)") (class "Default")
      (node (ref "DIG8") (pin "A6") (pinfunction "-6_A6") (pintype "passive"))
    )
    (net (code "305") (name "unconnected-(DIG8--7-PadA7)") (class "Default")
      (node (ref "DIG8") (pin "A7") (pinfunction "-7_A7") (pintype "passive"))
    )
    (net (code "306") (name "unconnected-(DIG8--8-PadA8)") (class "Default")
      (node (ref "DIG8") (pin "A8") (pinfunction "-8_A8") (pintype "passive"))
    )
    (net (code "307") (name "unconnected-(DIG8--9-PadA9)") (class "Default")
      (node (ref "DIG8") (pin "A9") (pinfunction "-9_A9") (pintype "passive"))
    )
    (net (code "308") (name "unconnected-(DIG8--10-PadA10)") (class "Default")
      (node (ref "DIG8") (pin "A10") (pinfunction "-10_A10") (pintype "passive"))
    )
    (net (code "309") (name "unconnected-(DIG8--11-PadA11)") (class "Default")
      (node (ref "DIG8") (pin "A11") (pinfunction "-11_A11") (pintype "passive"))
    )
    (net (code "310") (name "unconnected-(DIG8--12-PadA12)") (class "Default")
      (node (ref "DIG8") (pin "A12") (pinfunction "-12_A12") (pintype "passive"))
    )
    (net (code "311") (name "unconnected-(DIG8--13-PadA13)") (class "Default")
      (node (ref "DIG8") (pin "A13") (pinfunction "-13_A13") (pintype "passive"))
    )
    (net (code "312") (name "unconnected-(DIG8--14-PadA14)") (class "Default")
      (node (ref "DIG8") (pin "A14") (pinfunction "-14_A14") (pintype "passive"))
    )
    (net (code "313") (name "unconnected-(DIG8--15-PadA15)") (class "Default")
      (node (ref "DIG8") (pin "A15") (pinfunction "-15_A15") (pintype "passive"))
    )
    (net (code "314") (name "unconnected-(DIG8--16-PadA16)") (class "Default")
      (node (ref "DIG8") (pin "A16") (pinfunction "-16_A16") (pintype "passive"))
    )
    (net (code "315") (name "unconnected-(I2C--1-PadA1)") (class "Default")
      (node (ref "I2C") (pin "A1") (pinfunction "-1_A1") (pintype "passive"))
    )
    (net (code "316") (name "unconnected-(I2C--2-PadA2)") (class "Default")
      (node (ref "I2C") (pin "A2") (pinfunction "-2_A2") (pintype "passive"))
    )
    (net (code "317") (name "unconnected-(I2C--3-PadA3)") (class "Default")
      (node (ref "I2C") (pin "A3") (pinfunction "-3_A3") (pintype "passive"))
    )
    (net (code "318") (name "unconnected-(I2C--4-PadA4)") (class "Default")
      (node (ref "I2C") (pin "A4") (pinfunction "-4_A4") (pintype "passive"))
    )
    (net (code "319") (name "unconnected-(I2C--5-PadA5)") (class "Default")
      (node (ref "I2C") (pin "A5") (pinfunction "-5_A5") (pintype "passive"))
    )
    (net (code "320") (name "unconnected-(I2C--6-PadA6)") (class "Default")
      (node (ref "I2C") (pin "A6") (pinfunction "-6_A6") (pintype "passive"))
    )
    (net (code "321") (name "unconnected-(I2C--7-PadA7)") (class "Default")
      (node (ref "I2C") (pin "A7") (pinfunction "-7_A7") (pintype "passive"))
    )
    (net (code "322") (name "unconnected-(I2C--8-PadA8)") (class "Default")
      (node (ref "I2C") (pin "A8") (pinfunction "-8_A8") (pintype "passive"))
    )
    (net (code "323") (name "unconnected-(I2C--9-PadA9)") (class "Default")
      (node (ref "I2C") (pin "A9") (pinfunction "-9_A9") (pintype "passive"))
    )
    (net (code "324") (name "unconnected-(I2C--10-PadA10)") (class "Default")
      (node (ref "I2C") (pin "A10") (pinfunction "-10_A10") (pintype "passive"))
    )
    (net (code "325") (name "unconnected-(I2C--11-PadA11)") (class "Default")
      (node (ref "I2C") (pin "A11") (pinfunction "-11_A11") (pintype "passive"))
    )
    (net (code "326") (name "unconnected-(I2C--12-PadA12)") (class "Default")
      (node (ref "I2C") (pin "A12") (pinfunction "-12_A12") (pintype "passive"))
    )
    (net (code "327") (name "unconnected-(I2C--13-PadA13)") (class "Default")
      (node (ref "I2C") (pin "A13") (pinfunction "-13_A13") (pintype "passive"))
    )
    (net (code "328") (name "unconnected-(I2C--14-PadA14)") (class "Default")
      (node (ref "I2C") (pin "A14") (pinfunction "-14_A14") (pintype "passive"))
    )
    (net (code "329") (name "unconnected-(I2C--15-PadA15)") (class "Default")
      (node (ref "I2C") (pin "A15") (pinfunction "-15_A15") (pintype "passive"))
    )
    (net (code "330") (name "unconnected-(I2C--16-PadA16)") (class "Default")
      (node (ref "I2C") (pin "A16") (pinfunction "-16_A16") (pintype "passive"))
    )
    (net (code "331") (name "unconnected-(P7--1-PadA1)") (class "Default")
      (node (ref "P7") (pin "A1") (pinfunction "-1_A1") (pintype "passive"))
    )
    (net (code "332") (name "unconnected-(P7--2-PadA2)") (class "Default")
      (node (ref "P7") (pin "A2") (pinfunction "-2_A2") (pintype "passive"))
    )
    (net (code "333") (name "unconnected-(P7--3-PadA3)") (class "Default")
      (node (ref "P7") (pin "A3") (pinfunction "-3_A3") (pintype "passive"))
    )
    (net (code "334") (name "unconnected-(P7--4-PadA4)") (class "Default")
      (node (ref "P7") (pin "A4") (pinfunction "-4_A4") (pintype "passive"))
    )
    (net (code "335") (name "unconnected-(P7--5-PadA5)") (class "Default")
      (node (ref "P7") (pin "A5") (pinfunction "-5_A5") (pintype "passive"))
    )
    (net (code "336") (name "unconnected-(P7--6-PadA6)") (class "Default")
      (node (ref "P7") (pin "A6") (pinfunction "-6_A6") (pintype "passive"))
    )
    (net (code "337") (name "unconnected-(P7--7-PadA7)") (class "Default")
      (node (ref "P7") (pin "A7") (pinfunction "-7_A7") (pintype "passive"))
    )
    (net (code "338") (name "unconnected-(P7--8-PadA8)") (class "Default")
      (node (ref "P7") (pin "A8") (pinfunction "-8_A8") (pintype "passive"))
    )
    (net (code "339") (name "unconnected-(P7--9-PadA9)") (class "Default")
      (node (ref "P7") (pin "A9") (pinfunction "-9_A9") (pintype "passive"))
    )
    (net (code "340") (name "unconnected-(P7--10-PadA10)") (class "Default")
      (node (ref "P7") (pin "A10") (pinfunction "-10_A10") (pintype "passive"))
    )
    (net (code "341") (name "unconnected-(P7--11-PadA11)") (class "Default")
      (node (ref "P7") (pin "A11") (pinfunction "-11_A11") (pintype "passive"))
    )
    (net (code "342") (name "unconnected-(P7--12-PadA12)") (class "Default")
      (node (ref "P7") (pin "A12") (pinfunction "-12_A12") (pintype "passive"))
    )
    (net (code "343") (name "unconnected-(P7--13-PadA13)") (class "Default")
      (node (ref "P7") (pin "A13") (pinfunction "-13_A13") (pintype "passive"))
    )
    (net (code "344") (name "unconnected-(P7--14-PadA14)") (class "Default")
      (node (ref "P7") (pin "A14") (pinfunction "-14_A14") (pintype "passive"))
    )
    (net (code "345") (name "unconnected-(P7--15-PadA15)") (class "Default")
      (node (ref "P7") (pin "A15") (pinfunction "-15_A15") (pintype "passive"))
    )
    (net (code "346") (name "unconnected-(P7--16-PadA16)") (class "Default")
      (node (ref "P7") (pin "A16") (pinfunction "-16_A16") (pintype "passive"))
    )
    (net (code "347") (name "unconnected-(POWER-B-1-PadB1)") (class "Default")
      (node (ref "POWER") (pin "B1") (pinfunction "B-1_B1") (pintype "passive"))
    )
    (net (code "348") (name "unconnected-(POWER-B-2-PadB2)") (class "Default")
      (node (ref "POWER") (pin "B2") (pinfunction "B-2_B2") (pintype "passive"))
    )
    (net (code "349") (name "unconnected-(RASPBERRY--1-PadA1)") (class "Default")
      (node (ref "RASPBERRY") (pin "A1") (pinfunction "-1_A1") (pintype "passive"))
    )
    (net (code "350") (name "unconnected-(RASPBERRY--2-PadA2)") (class "Default")
      (node (ref "RASPBERRY") (pin "A2") (pinfunction "-2_A2") (pintype "passive"))
    )
    (net (code "351") (name "unconnected-(RASPBERRY--3-PadA3)") (class "Default")
      (node (ref "RASPBERRY") (pin "A3") (pinfunction "-3_A3") (pintype "passive"))
    )
    (net (code "352") (name "unconnected-(RASPBERRY--4-PadA4)") (class "Default")
      (node (ref "RASPBERRY") (pin "A4") (pinfunction "-4_A4") (pintype "passive"))
    )
    (net (code "353") (name "unconnected-(RASPBERRY--5-PadA5)") (class "Default")
      (node (ref "RASPBERRY") (pin "A5") (pinfunction "-5_A5") (pintype "passive"))
    )
    (net (code "354") (name "unconnected-(RASPBERRY--6-PadA6)") (class "Default")
      (node (ref "RASPBERRY") (pin "A6") (pinfunction "-6_A6") (pintype "passive"))
    )
    (net (code "355") (name "unconnected-(RASPBERRY--7-PadA7)") (class "Default")
      (node (ref "RASPBERRY") (pin "A7") (pinfunction "-7_A7") (pintype "passive"))
    )
    (net (code "356") (name "unconnected-(RASPBERRY--8-PadA8)") (class "Default")
      (node (ref "RASPBERRY") (pin "A8") (pinfunction "-8_A8") (pintype "passive"))
    )
    (net (code "357") (name "unconnected-(RASPBERRY--9-PadA9)") (class "Default")
      (node (ref "RASPBERRY") (pin "A9") (pinfunction "-9_A9") (pintype "passive"))
    )
    (net (code "358") (name "unconnected-(RASPBERRY--10-PadA10)") (class "Default")
      (node (ref "RASPBERRY") (pin "A10") (pinfunction "-10_A10") (pintype "passive"))
    )
    (net (code "359") (name "unconnected-(RASPBERRY--11-PadA11)") (class "Default")
      (node (ref "RASPBERRY") (pin "A11") (pinfunction "-11_A11") (pintype "passive"))
    )
    (net (code "360") (name "unconnected-(RASPBERRY--12-PadA12)") (class "Default")
      (node (ref "RASPBERRY") (pin "A12") (pinfunction "-12_A12") (pintype "passive"))
    )
    (net (code "361") (name "unconnected-(RASPBERRY--13-PadA13)") (class "Default")
      (node (ref "RASPBERRY") (pin "A13") (pinfunction "-13_A13") (pintype "passive"))
    )
    (net (code "362") (name "unconnected-(RASPBERRY--14-PadA14)") (class "Default")
      (node (ref "RASPBERRY") (pin "A14") (pinfunction "-14_A14") (pintype "passive"))
    )
    (net (code "363") (name "unconnected-(RASPBERRY--15-PadA15)") (class "Default")
      (node (ref "RASPBERRY") (pin "A15") (pinfunction "-15_A15") (pintype "passive"))
    )
    (net (code "364") (name "unconnected-(RASPBERRY--16-PadA16)") (class "Default")
      (node (ref "RASPBERRY") (pin "A16") (pinfunction "-16_A16") (pintype "passive"))
    )
  )
)
